# M2FS_FLS_Data_Formatter_8_14_2012.net
KiCad netlist of a schematic drawn in Altium Designer
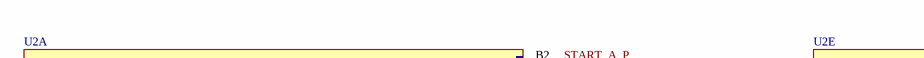
[diagram p0: M2FS FLS Data Formatter 8_14_2012.SchDoc, top right]
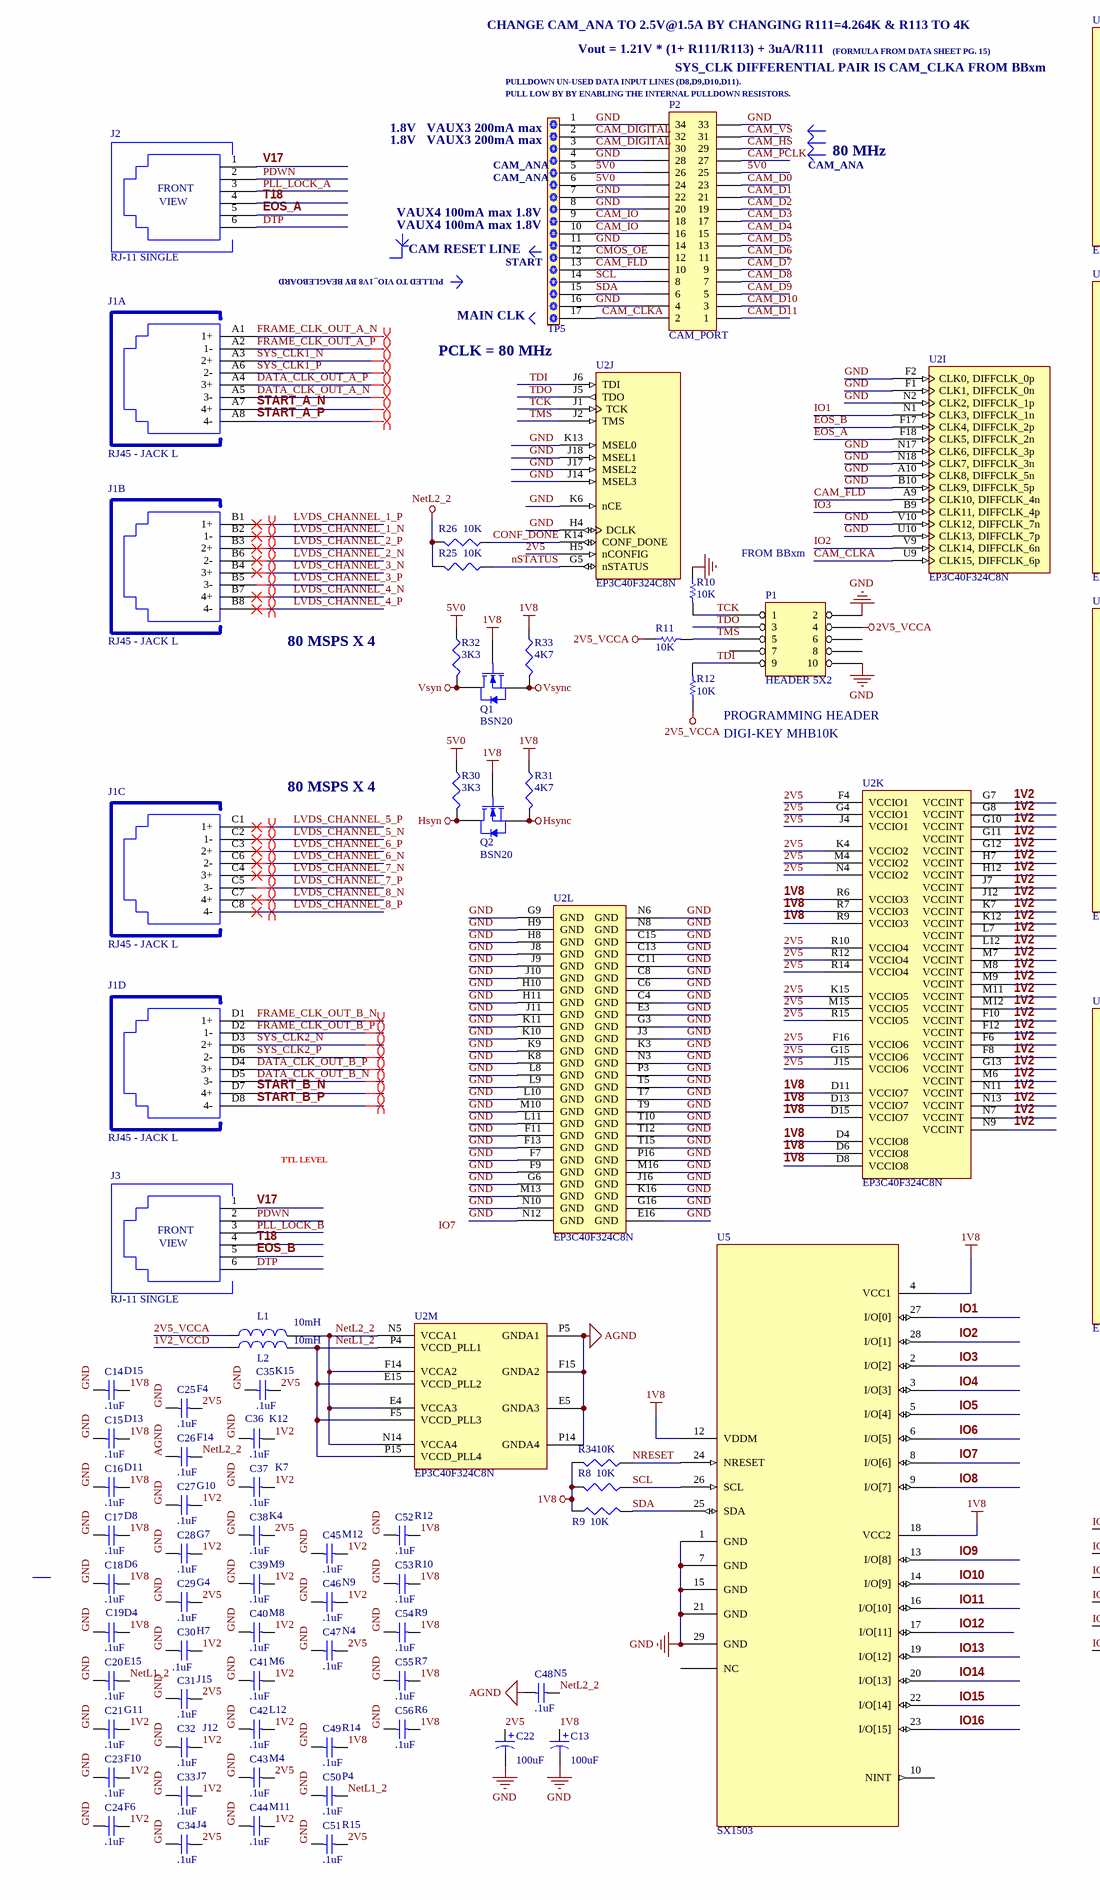
[diagram p1: M2FS FLS Data Formatter 8_14_2012.SchDoc, bottom left]
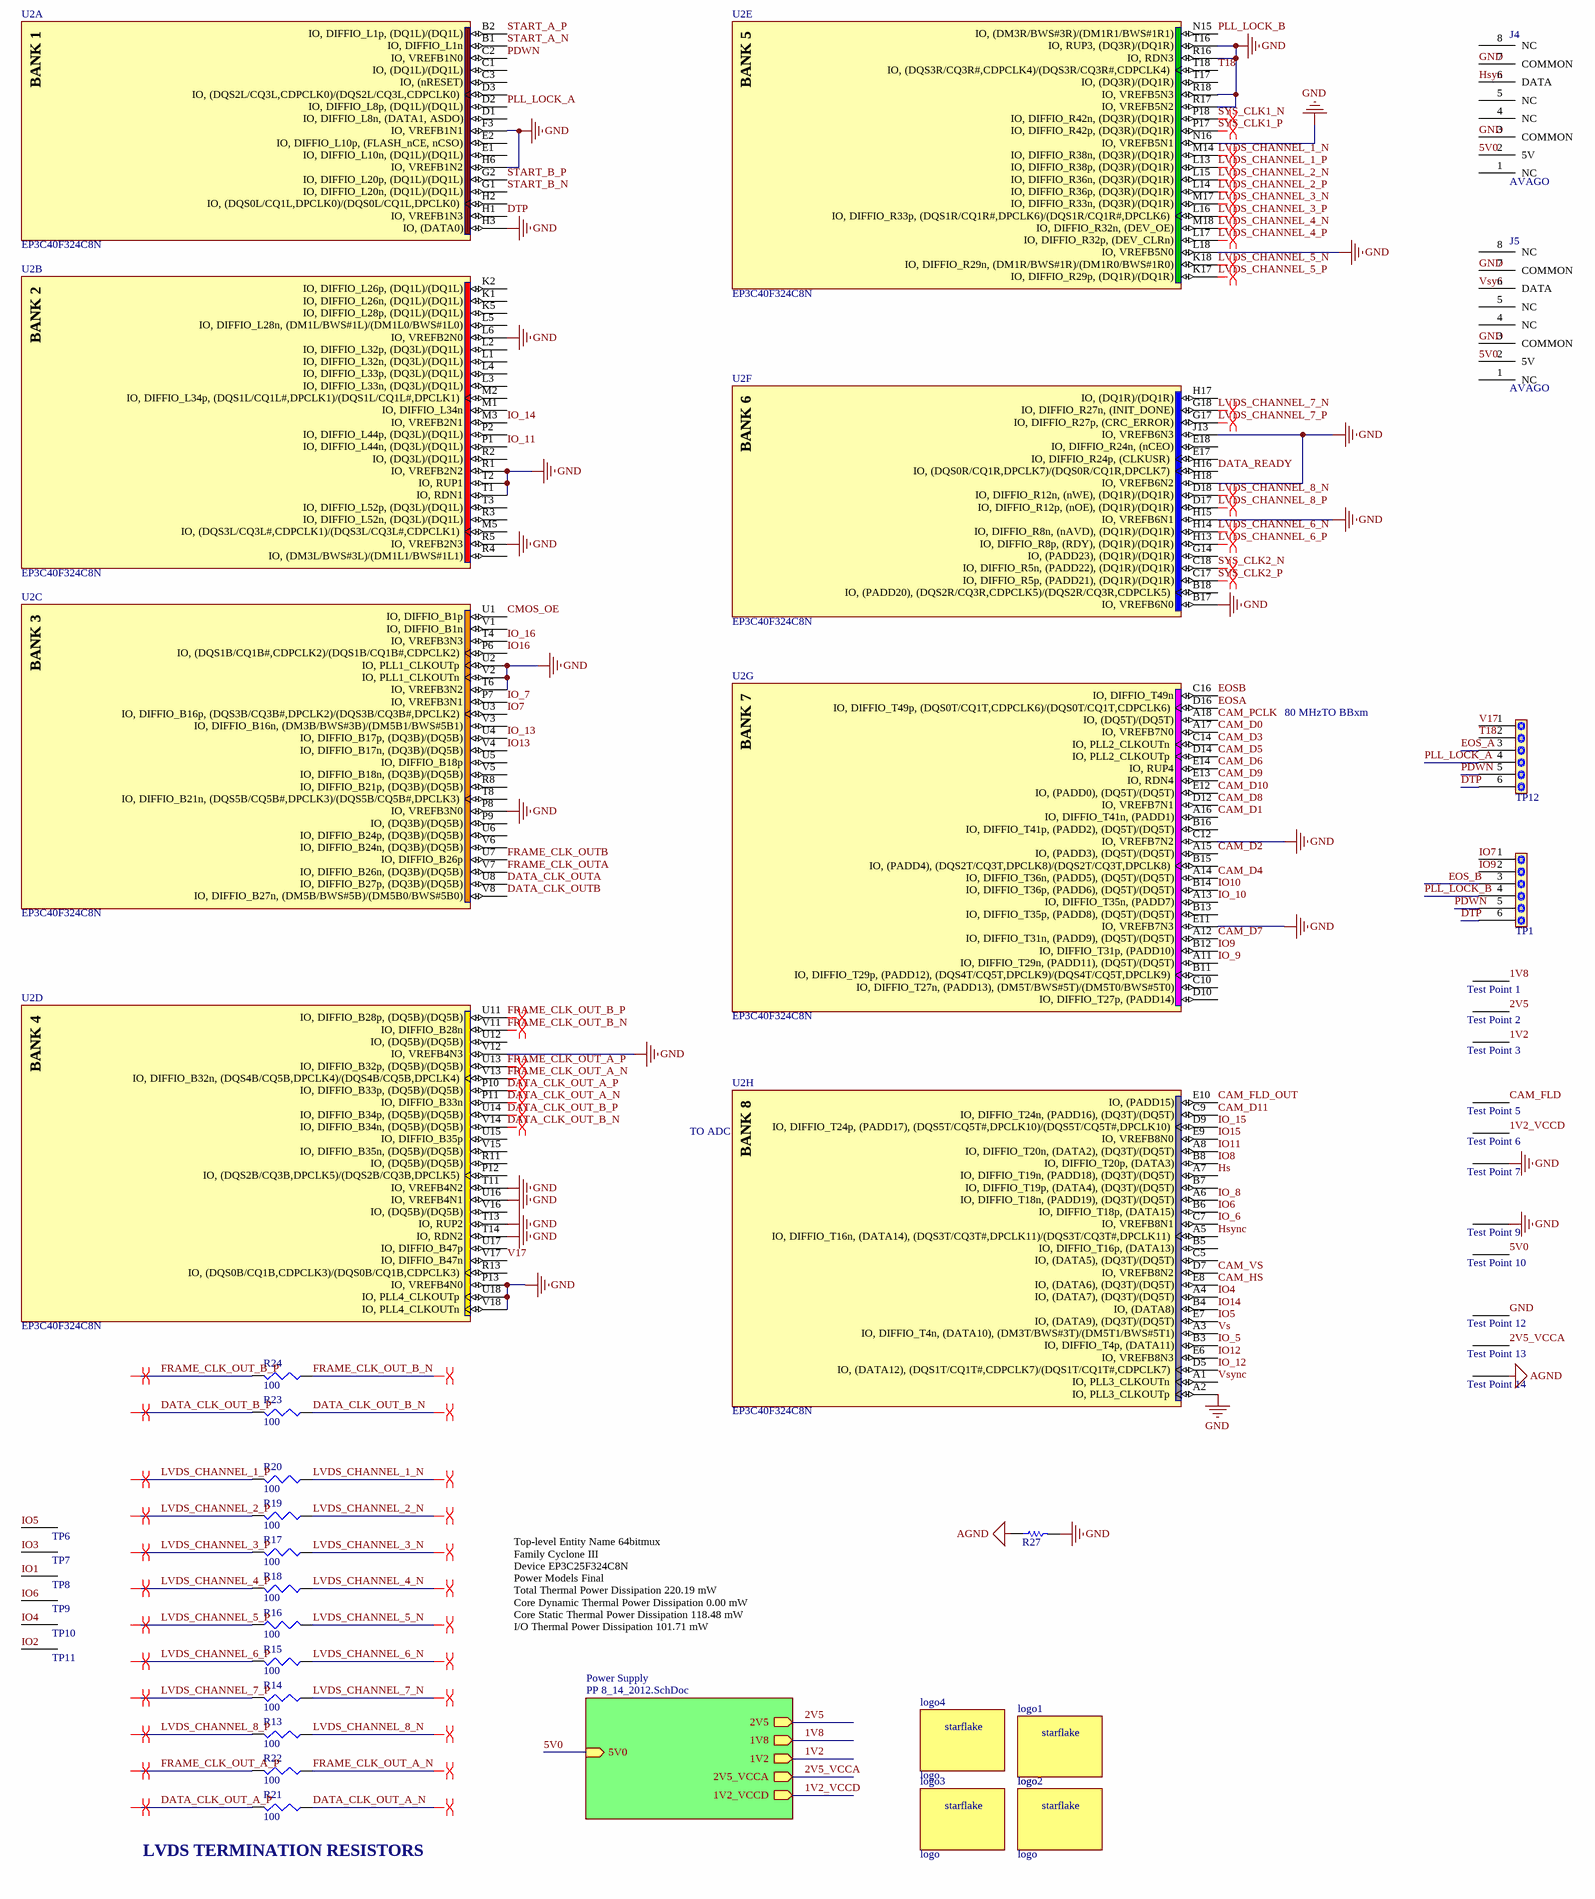
[diagram p2: M2FS FLS Data Formatter 8_14_2012.SchDoc, bottom right]

(export (version "E")
  (design (tool "Eeschema 10.0.6"))
  (components
    (comp (ref "C13")
      (value "100uF")
      (footprint "1206")
      (description "CAP TANT 100UF 10V 20% 1210")
      (fields (field (name "PUBLISHER") "Altium Limited"))
      (libsource (lib "Miscellaneous Devices") (part "Cap Pol3"))
    )
    (comp (ref "C14")
      (value ".1uF")
      (footprint "0402 slim")
      (description "CAP CER 0.1UF 25V Y5V 0805")
      (fields
        (field (name "BALL") "D15")
        (field (name "Comment") "0.1uF")
        (field (name "PUBLISHER") "Altium Limited")
      )
      (libsource (lib "Miscellaneous Devices") (part "Cap Semi"))
    )
    (comp (ref "C15")
      (value ".1uF")
      (footprint "0402 slim")
      (description "CAP CER 0.1UF 25V Y5V 0805")
      (fields
        (field (name "BALL") "D13")
        (field (name "Comment") "0.1uF")
        (field (name "PUBLISHER") "Altium Limited")
      )
      (libsource (lib "Miscellaneous Devices") (part "Cap Semi"))
    )
    (comp (ref "C16")
      (value ".1uF")
      (footprint "0402 slim-B")
      (description "CAP CER 0.1UF 25V Y5V 0805")
      (fields
        (field (name "BALL") "D11")
        (field (name "Comment") "0.1uF")
        (field (name "PUBLISHER") "Altium Limited")
      )
      (libsource (lib "Miscellaneous Devices") (part "Cap Semi"))
    )
    (comp (ref "C17")
      (value ".1uF")
      (footprint "0402 slim")
      (description "CAP CER 0.1UF 25V Y5V 0805")
      (fields
        (field (name "BALL") "D8")
        (field (name "Comment") "0.1uF")
        (field (name "PUBLISHER") "Altium Limited")
      )
      (libsource (lib "Miscellaneous Devices") (part "Cap Semi"))
    )
    (comp (ref "C18")
      (value ".1uF")
      (footprint "0402 slim-B")
      (description "CAP CER 0.1UF 25V Y5V 0805")
      (fields
        (field (name "BALL") "D6")
        (field (name "Comment") "0.1uF")
        (field (name "PUBLISHER") "Altium Limited")
      )
      (libsource (lib "Miscellaneous Devices") (part "Cap Semi"))
    )
    (comp (ref "C19")
      (value ".1uF")
      (footprint "0402 slim")
      (description "CAP CER 0.1UF 25V Y5V 0805")
      (fields
        (field (name "BALL") "D4")
        (field (name "Comment") "0.1uF")
        (field (name "PUBLISHER") "Altium Limited")
      )
      (libsource (lib "Miscellaneous Devices") (part "Cap Semi"))
    )
    (comp (ref "C20")
      (value ".1uF")
      (footprint "0402 slim-B")
      (description "CAP CER 0.1UF 25V Y5V 0805")
      (fields
        (field (name "BALL") "E15")
        (field (name "Comment") "0.1uF")
        (field (name "PUBLISHER") "Altium Limited")
      )
      (libsource (lib "Miscellaneous Devices") (part "Cap Semi"))
    )
    (comp (ref "C21")
      (value ".1uF")
      (footprint "0402 slim")
      (description "CAP CER 0.1UF 25V Y5V 0805")
      (fields
        (field (name "BALL") "G11")
        (field (name "Comment") "0.1uF")
        (field (name "PUBLISHER") "Altium Limited")
      )
      (libsource (lib "Miscellaneous Devices") (part "Cap Semi"))
    )
    (comp (ref "C22")
      (value "100uF")
      (footprint "1206")
      (description "CAP TANT 100UF 10V 20% 1210")
      (fields (field (name "PUBLISHER") "Altium Limited"))
      (libsource (lib "Miscellaneous Devices") (part "Cap Pol3"))
    )
    (comp (ref "C23")
      (value ".1uF")
      (footprint "0402 slim-B")
      (description "CAP CER 0.1UF 25V Y5V 0805")
      (fields
        (field (name "BALL") "F10")
        (field (name "Comment") "0.1uF")
        (field (name "PUBLISHER") "Altium Limited")
      )
      (libsource (lib "Miscellaneous Devices") (part "Cap Semi"))
    )
    (comp (ref "C24")
      (value ".1uF")
      (footprint "0402 slim")
      (description "CAP CER 0.1UF 25V Y5V 0805")
      (fields
        (field (name "BALL") "F6")
        (field (name "Comment") "0.1uF")
        (field (name "PUBLISHER") "Altium Limited")
      )
      (libsource (lib "Miscellaneous Devices") (part "Cap Semi"))
    )
    (comp (ref "C25")
      (value ".1uF")
      (footprint "0402 slim")
      (description "CAP CER 0.1UF 25V Y5V 0805")
      (fields
        (field (name "BALL") "F4")
        (field (name "Comment") "0.1uF")
        (field (name "PUBLISHER") "Altium Limited")
      )
      (libsource (lib "Miscellaneous Devices") (part "Cap Semi"))
    )
    (comp (ref "C26")
      (value ".1uF")
      (footprint "0402 slim")
      (description "CAP CER 0.1UF 25V Y5V 0805")
      (fields
        (field (name "BALL") "F14")
        (field (name "Comment") "0.1uF")
        (field (name "PUBLISHER") "Altium Limited")
      )
      (libsource (lib "Miscellaneous Devices") (part "Cap Semi"))
    )
    (comp (ref "C27")
      (value ".1uF")
      (footprint "0402 slim")
      (description "CAP CER 0.1UF 25V Y5V 0805")
      (fields
        (field (name "BALL") "G10")
        (field (name "Comment") "0.1uF")
        (field (name "PUBLISHER") "Altium Limited")
      )
      (libsource (lib "Miscellaneous Devices") (part "Cap Semi"))
    )
    (comp (ref "C28")
      (value ".1uF")
      (footprint "0402 slim-B")
      (description "CAP CER 0.1UF 25V Y5V 0805")
      (fields
        (field (name "BALL") "G7")
        (field (name "Comment") "0.1uF")
        (field (name "PUBLISHER") "Altium Limited")
      )
      (libsource (lib "Miscellaneous Devices") (part "Cap Semi"))
    )
    (comp (ref "C29")
      (value ".1uF")
      (footprint "0402 slim")
      (description "CAP CER 0.1UF 25V Y5V 0805")
      (fields
        (field (name "BALL") "G4")
        (field (name "Comment") "0.1uF")
        (field (name "PUBLISHER") "Altium Limited")
      )
      (libsource (lib "Miscellaneous Devices") (part "Cap Semi"))
    )
    (comp (ref "C30")
      (value ".1uF")
      (footprint "0402 slim-B")
      (description "CAP CER 0.1UF 25V Y5V 0805")
      (fields
        (field (name "BALL") "H7")
        (field (name "Comment") "0.1uF")
        (field (name "PUBLISHER") "Altium Limited")
      )
      (libsource (lib "Miscellaneous Devices") (part "Cap Semi"))
    )
    (comp (ref "C31")
      (value ".1uF")
      (footprint "0402 slim")
      (description "CAP CER 0.1UF 25V Y5V 0805")
      (fields
        (field (name "BALL") "J15")
        (field (name "Comment") "0.1uF")
        (field (name "PUBLISHER") "Altium Limited")
      )
      (libsource (lib "Miscellaneous Devices") (part "Cap Semi"))
    )
    (comp (ref "C32")
      (value ".1uF")
      (footprint "0402 slim-B")
      (description "CAP CER 0.1UF 25V Y5V 0805")
      (fields
        (field (name "BALL") "J12")
        (field (name "Comment") "0.1uF")
        (field (name "PUBLISHER") "Altium Limited")
      )
      (libsource (lib "Miscellaneous Devices") (part "Cap Semi"))
    )
    (comp (ref "C33")
      (value ".1uF")
      (footprint "0402 slim-B")
      (description "CAP CER 0.1UF 25V Y5V 0805")
      (fields
        (field (name "BALL") "J7")
        (field (name "Comment") "0.1uF")
        (field (name "PUBLISHER") "Altium Limited")
      )
      (libsource (lib "Miscellaneous Devices") (part "Cap Semi"))
    )
    (comp (ref "C34")
      (value ".1uF")
      (footprint "0402 slim")
      (description "CAP CER 0.1UF 25V Y5V 0805")
      (fields
        (field (name "C34") "J4")
        (field (name "Comment") "0.1uF")
        (field (name "PUBLISHER") "Altium Limited")
      )
      (libsource (lib "Miscellaneous Devices") (part "Cap Semi"))
    )
    (comp (ref "C35")
      (value ".1uF")
      (footprint "0402 slim")
      (description "CAP CER 0.1UF 25V Y5V 0805")
      (fields
        (field (name "BALL") "K15")
        (field (name "Comment") "0.1uF")
        (field (name "PUBLISHER") "Altium Limited")
      )
      (libsource (lib "Miscellaneous Devices") (part "Cap Semi"))
    )
    (comp (ref "C36")
      (value ".1uF")
      (footprint "0402 slim")
      (description "CAP CER 0.1UF 25V Y5V 0805")
      (fields
        (field (name "BALL") "K12")
        (field (name "Comment") "0.1uF")
        (field (name "PUBLISHER") "Altium Limited")
      )
      (libsource (lib "Miscellaneous Devices") (part "Cap Semi"))
    )
    (comp (ref "C37")
      (value ".1uF")
      (footprint "0402 slim-B")
      (description "CAP CER 0.1UF 25V Y5V 0805")
      (fields
        (field (name "BALL") "K7")
        (field (name "Comment") "0.1uF")
        (field (name "PUBLISHER") "Altium Limited")
      )
      (libsource (lib "Miscellaneous Devices") (part "Cap Semi"))
    )
    (comp (ref "C38")
      (value ".1uF")
      (footprint "0402 slim")
      (description "CAP CER 0.1UF 25V Y5V 0805")
      (fields
        (field (name "BALL") "K4")
        (field (name "Comment") "0.1uF")
        (field (name "PUBLISHER") "Altium Limited")
      )
      (libsource (lib "Miscellaneous Devices") (part "Cap Semi"))
    )
    (comp (ref "C39")
      (value ".1uF")
      (footprint "0402 slim")
      (description "CAP CER 0.1UF 25V Y5V 0805")
      (fields
        (field (name "BALL") "M9")
        (field (name "Comment") "0.1uF")
        (field (name "PUBLISHER") "Altium Limited")
      )
      (libsource (lib "Miscellaneous Devices") (part "Cap Semi"))
    )
    (comp (ref "C40")
      (value ".1uF")
      (footprint "0402 slim-B")
      (description "CAP CER 0.1UF 25V Y5V 0805")
      (fields
        (field (name "BALL") "M8")
        (field (name "Comment") "0.1uF")
        (field (name "PUBLISHER") "Altium Limited")
      )
      (libsource (lib "Miscellaneous Devices") (part "Cap Semi"))
    )
    (comp (ref "C41")
      (value ".1uF")
      (footprint "0402 slim")
      (description "CAP CER 0.1UF 25V Y5V 0805")
      (fields
        (field (name "BALL") "M6")
        (field (name "Comment") "0.1uF")
        (field (name "PUBLISHER") "Altium Limited")
      )
      (libsource (lib "Miscellaneous Devices") (part "Cap Semi"))
    )
    (comp (ref "C42")
      (value ".1uF")
      (footprint "0402 slim")
      (description "CAP CER 0.1UF 25V Y5V 0805")
      (fields
        (field (name "BALL") "L12")
        (field (name "Comment") "0.1uF")
        (field (name "PUBLISHER") "Altium Limited")
      )
      (libsource (lib "Miscellaneous Devices") (part "Cap Semi"))
    )
    (comp (ref "C43")
      (value ".1uF")
      (footprint "0402 slim")
      (description "CAP CER 0.1UF 25V Y5V 0805")
      (fields
        (field (name "BALL") "M4")
        (field (name "Comment") "0.1uF")
        (field (name "PUBLISHER") "Altium Limited")
      )
      (libsource (lib "Miscellaneous Devices") (part "Cap Semi"))
    )
    (comp (ref "C44")
      (value ".1uF")
      (footprint "0402 slim")
      (description "CAP CER 0.1UF 25V Y5V 0805")
      (fields
        (field (name "BALL") "M11")
        (field (name "Comment") "0.1uF")
        (field (name "PUBLISHER") "Altium Limited")
      )
      (libsource (lib "Miscellaneous Devices") (part "Cap Semi"))
    )
    (comp (ref "C45")
      (value ".1uF")
      (footprint "0402 slim-B")
      (description "CAP CER 0.1UF 25V Y5V 0805")
      (fields
        (field (name "BALL") "M12")
        (field (name "Comment") "0.1uF")
        (field (name "PUBLISHER") "Altium Limited")
      )
      (libsource (lib "Miscellaneous Devices") (part "Cap Semi"))
    )
    (comp (ref "C46")
      (value ".1uF")
      (footprint "0402 slim")
      (description "CAP CER 0.1UF 25V Y5V 0805")
      (fields
        (field (name "BALL") "N9")
        (field (name "Comment") "0.1uF")
        (field (name "PUBLISHER") "Altium Limited")
      )
      (libsource (lib "Miscellaneous Devices") (part "Cap Semi"))
    )
    (comp (ref "C47")
      (value ".1uF")
      (footprint "0402 slim")
      (description "CAP CER 0.1UF 25V Y5V 0805")
      (fields
        (field (name "BAL") "N4")
        (field (name "Comment") "0.1uF")
        (field (name "PUBLISHER") "Altium Limited")
      )
      (libsource (lib "Miscellaneous Devices") (part "Cap Semi"))
    )
    (comp (ref "C48")
      (value ".1uF")
      (footprint "0402 slim")
      (description "CAP CER 0.1UF 25V Y5V 0805")
      (fields
        (field (name "BALL") "N5")
        (field (name "Comment") "0.1uF")
        (field (name "PUBLISHER") "Altium Limited")
      )
      (libsource (lib "Miscellaneous Devices") (part "Cap Semi"))
    )
    (comp (ref "C49")
      (value ".1uF")
      (footprint "0402 slim")
      (description "CAP CER 0.1UF 25V Y5V 0805")
      (fields
        (field (name "BALL") "R14")
        (field (name "Comment") "0.1uF")
        (field (name "PUBLISHER") "Altium Limited")
      )
      (libsource (lib "Miscellaneous Devices") (part "Cap Semi"))
    )
    (comp (ref "C50")
      (value ".1uF")
      (footprint "0402 slim")
      (description "CAP CER 0.1UF 25V Y5V 0805")
      (fields
        (field (name "BALL") "P4")
        (field (name "Comment") "0.1uF")
        (field (name "PUBLISHER") "Altium Limited")
      )
      (libsource (lib "Miscellaneous Devices") (part "Cap Semi"))
    )
    (comp (ref "C51")
      (value ".1uF")
      (footprint "0402 slim")
      (description "CAP CER 0.1UF 25V Y5V 0805")
      (fields
        (field (name "BALL") "R15")
        (field (name "Comment") "0.1uF")
        (field (name "PUBLISHER") "Altium Limited")
      )
      (libsource (lib "Miscellaneous Devices") (part "Cap Semi"))
    )
    (comp (ref "C52")
      (value ".1uF")
      (footprint "0402 slim")
      (description "CAP CER 0.1UF 25V Y5V 0805")
      (fields
        (field (name "BALL") "R12")
        (field (name "Comment") "0.1uF")
        (field (name "PUBLISHER") "Altium Limited")
      )
      (libsource (lib "Miscellaneous Devices") (part "Cap Semi"))
    )
    (comp (ref "C53")
      (value ".1uF")
      (footprint "0402 slim")
      (description "CAP CER 0.1UF 25V Y5V 0805")
      (fields
        (field (name "BALL") "R10")
        (field (name "Comment") "0.1uF")
        (field (name "PUBLISHER") "Altium Limited")
      )
      (libsource (lib "Miscellaneous Devices") (part "Cap Semi"))
    )
    (comp (ref "C54")
      (value ".1uF")
      (footprint "0402 slim")
      (description "CAP CER 0.1UF 25V Y5V 0805")
      (fields
        (field (name "BALL") "R9")
        (field (name "Comment") "0.1uF")
        (field (name "PUBLISHER") "Altium Limited")
      )
      (libsource (lib "Miscellaneous Devices") (part "Cap Semi"))
    )
    (comp (ref "C55")
      (value ".1uF")
      (footprint "0402 slim")
      (description "CAP CER 0.1UF 25V Y5V 0805")
      (fields
        (field (name "BALL") "R7")
        (field (name "Comment") "0.1uF")
        (field (name "PUBLISHER") "Altium Limited")
      )
      (libsource (lib "Miscellaneous Devices") (part "Cap Semi"))
    )
    (comp (ref "C56")
      (value ".1uF")
      (footprint "0402 slim")
      (description "CAP CER 0.1UF 25V Y5V 0805")
      (fields
        (field (name "BALL") "R6")
        (field (name "Comment") "0.1uF")
        (field (name "PUBLISHER") "Altium Limited")
      )
      (libsource (lib "Miscellaneous Devices") (part "Cap Semi"))
    )
    (comp (ref "J1")
      (value "RJ45 - JACK L")
      (footprint "5558503-1 Quad RJ45 Jack")
      (description "CONN MOD JACK 4PORT5 8-8 SHLD PCB")
      (fields
        (field (name "DIGI-KEY PART NUMBER") "A31470-ND")
        (field (name "MANUFACTURER") "TE Connectivity")
      )
      (libsource (lib "FLS Data Formatter 8_14_2012") (part "RJ45 - JACK L"))
    )
    (comp (ref "J2")
      (value "RJ-11 SINGLE")
      (footprint "RJ11 - 5555140-1")
      (description "RJ-11 JACK")
      (libsource (lib "FLS Data Formatter 8_14_2012") (part "RJ-11 SINGLE"))
    )
    (comp (ref "J3")
      (value "RJ-11 SINGLE")
      (footprint "RJ11 - 5555140-1")
      (description "RJ-11 JACK")
      (libsource (lib "FLS Data Formatter 8_14_2012") (part "RJ-11 SINGLE"))
    )
    (comp (ref "J4")
      (value "AVAGO")
      (footprint "HFBR-2412Z")
      (libsource (lib "FLS Data Formatter 8_14_2012") (part "HFBR-2412"))
    )
    (comp (ref "J5")
      (value "AVAGO")
      (footprint "HFBR-2412Z")
      (libsource (lib "FLS Data Formatter 8_14_2012") (part "HFBR-2412"))
    )
    (comp (ref "L1")
      (value "10mH")
      (footprint "0805")
      (description "Inductor")
      (fields (field (name "PUBLISHER") "Altium Limited"))
      (libsource (lib "Miscellaneous Devices") (part "Inductor"))
    )
    (comp (ref "L2")
      (value "10mH")
      (footprint "0805")
      (description "Inductor")
      (fields (field (name "PUBLISHER") "Altium Limited"))
      (libsource (lib "Miscellaneous Devices") (part "Inductor"))
    )
    (comp (ref "logo1")
      (value "logo")
      (footprint "STARFLAKE")
      (libsource (lib "FLS Data Formatter 8_14_2012") (part "starflake"))
    )
    (comp (ref "logo2")
      (value "logo")
      (footprint "STARFLAKE")
      (libsource (lib "FLS Data Formatter 8_14_2012") (part "starflake"))
    )
    (comp (ref "logo3")
      (value "logo")
      (footprint "STARFLAKE")
      (libsource (lib "FLS Data Formatter 8_14_2012") (part "starflake"))
    )
    (comp (ref "logo4")
      (value "logo")
      (footprint "STARFLAKE")
      (libsource (lib "FLS Data Formatter 8_14_2012") (part "starflake"))
    )
    (comp (ref "P1")
      (value "HEADER 5X2")
      (footprint "HDR2X5")
      (libsource (lib "FLS Data Formatter 8_14_2012") (part "HEADER 5X2"))
    )
    (comp (ref "P2")
      (value "CAM_PORT")
      (footprint "CON34_.05X.05")
      (description "Header, 17-Pin, Dual row")
      (fields (field (name "PUBLISHER") "Altium Limited"))
      (libsource (lib "Miscellaneous Connectors") (part "Header 17X2"))
    )
    (comp (ref "Q1")
      (value "BSN20")
      (footprint "SOT23")
      (description "N-channel Enhancement Mode FET")
      (fields (field (name "PUBLISHER") "Altium Limited"))
      (libsource (lib "Philips Discrete MOSFET - Low Power") (part "BSN20"))
    )
    (comp (ref "Q2")
      (value "BSN20")
      (footprint "SOT23")
      (description "N-channel Enhancement Mode FET")
      (fields (field (name "PUBLISHER") "Altium Limited"))
      (libsource (lib "Philips Discrete MOSFET - Low Power") (part "BSN20"))
    )
    (comp (ref "R8")
      (value "10K")
      (footprint "0402 slim")
      (libsource (lib "FLS Data Formatter 8_14_2012") (part "RES1"))
    )
    (comp (ref "R9")
      (value "10K")
      (footprint "0402 slim")
      (libsource (lib "FLS Data Formatter 8_14_2012") (part "RES1"))
    )
    (comp (ref "R10")
      (value "10K")
      (footprint "6-0805")
      (fields
        (field (name "MANUFACTURER") "Panasonic")
        (field (name "DIGIKEY PART #") "P10KATR-ND")
        (field (name "PUBLISHER") "Altium Limited")
      )
      (libsource (lib "Panasonic Resistor") (part "ERJ6RK"))
    )
    (comp (ref "R11")
      (value "10K")
      (footprint "6-0805")
      (fields
        (field (name "MANUFACTURER") "Panasonic")
        (field (name "DIGIKEY PART #") "P10KATR-ND")
        (field (name "PUBLISHER") "Altium Limited")
      )
      (libsource (lib "Panasonic Resistor") (part "ERJ6RK"))
    )
    (comp (ref "R12")
      (value "10K")
      (footprint "6-0805")
      (fields
        (field (name "MANUFACTURER") "Panasonic")
        (field (name "DIGIKEY PART #") "P10KATR-ND")
        (field (name "PUBLISHER") "Altium Limited")
      )
      (libsource (lib "Panasonic Resistor") (part "ERJ6RK"))
    )
    (comp (ref "R13")
      (value "100")
      (footprint "0402 slim")
      (libsource (lib "FLS Data Formatter 8_14_2012") (part "RES1"))
    )
    (comp (ref "R14")
      (value "100")
      (footprint "0402 slim")
      (libsource (lib "FLS Data Formatter 8_14_2012") (part "RES1"))
    )
    (comp (ref "R15")
      (value "100")
      (footprint "0402 slim")
      (libsource (lib "FLS Data Formatter 8_14_2012") (part "RES1"))
    )
    (comp (ref "R16")
      (value "100")
      (footprint "0402 slim")
      (libsource (lib "FLS Data Formatter 8_14_2012") (part "RES1"))
    )
    (comp (ref "R17")
      (value "100")
      (footprint "0402 one-of")
      (libsource (lib "FLS Data Formatter 8_14_2012") (part "RES1"))
    )
    (comp (ref "R18")
      (value "100")
      (footprint "0402 slim")
      (libsource (lib "FLS Data Formatter 8_14_2012") (part "RES1"))
    )
    (comp (ref "R19")
      (value "100")
      (footprint "0402 slim")
      (libsource (lib "FLS Data Formatter 8_14_2012") (part "RES1"))
    )
    (comp (ref "R20")
      (value "100")
      (footprint "0402 slim")
      (libsource (lib "FLS Data Formatter 8_14_2012") (part "RES1"))
    )
    (comp (ref "R21")
      (value "100")
      (footprint "0402 slim")
      (libsource (lib "FLS Data Formatter 8_14_2012") (part "RES1"))
    )
    (comp (ref "R22")
      (value "100")
      (footprint "0402 slim")
      (libsource (lib "FLS Data Formatter 8_14_2012") (part "RES1"))
    )
    (comp (ref "R23")
      (value "100")
      (footprint "0402 slim")
      (libsource (lib "FLS Data Formatter 8_14_2012") (part "RES1"))
    )
    (comp (ref "R24")
      (value "100")
      (footprint "0402 slim")
      (libsource (lib "FLS Data Formatter 8_14_2012") (part "RES1"))
    )
    (comp (ref "R25")
      (value "10K")
      (footprint "0805")
      (libsource (lib "FLS Data Formatter 8_14_2012") (part "RES1"))
    )
    (comp (ref "R26")
      (value "10K")
      (footprint "0805")
      (libsource (lib "FLS Data Formatter 8_14_2012") (part "RES1"))
    )
    (comp (ref "R27")
      (value "0R5 0805(2012)")
      (footprint "RESC0805(2012)_N")
      (description "0R5 0805 (2012 Metric)")
      (fields (field (name "TOLERANCE") "1%") (field (name "POWER") "None"))
      (libsource (lib "Altium Vault") (part "CMP-1013-00001-1"))
    )
    (comp (ref "R30")
      (value "3K3")
      (footprint "0805")
      (libsource (lib "FLS Data Formatter 8_14_2012") (part "RES1"))
    )
    (comp (ref "R31")
      (value "4K7")
      (footprint "0805")
      (libsource (lib "FLS Data Formatter 8_14_2012") (part "RES1"))
    )
    (comp (ref "R32")
      (value "3K3")
      (footprint "0805")
      (libsource (lib "FLS Data Formatter 8_14_2012") (part "RES1"))
    )
    (comp (ref "R33")
      (value "4K7")
      (footprint "0805")
      (libsource (lib "FLS Data Formatter 8_14_2012") (part "RES1"))
    )
    (comp (ref "R34")
      (value "10K")
      (footprint "0402 slim")
      (libsource (lib "FLS Data Formatter 8_14_2012") (part "RES1"))
    )
    (comp (ref "Test Point 1") (value "TP-107") (libsource (lib "FLS ADC_A") (part "TP-107")))
    (comp (ref "Test Point 2") (value "TP-107") (libsource (lib "FLS ADC_A") (part "TP-107")))
    (comp (ref "Test Point 3") (value "TP-107") (libsource (lib "FLS ADC_A") (part "TP-107")))
    (comp (ref "Test Point 5") (value "TP-107") (libsource (lib "FLS ADC_A") (part "TP-107")))
    (comp (ref "Test Point 6")
      (value "TP-107")
      (footprint "TP-107")
      (libsource (lib "FLS ADC_A") (part "TP-107"))
    )
    (comp (ref "Test Point 7") (value "TP-107") (libsource (lib "FLS ADC_A") (part "TP-107")))
    (comp (ref "Test Point 9") (value "TP-107") (libsource (lib "FLS ADC_A") (part "TP-107")))
    (comp (ref "Test Point 10") (value "TP-107") (libsource (lib "FLS ADC_A") (part "TP-107")))
    (comp (ref "Test Point 12")
      (value "TP-107")
      (footprint "TP-107")
      (libsource (lib "FLS ADC_A") (part "TP-107"))
    )
    (comp (ref "Test Point 13")
      (value "TP-107")
      (footprint "TP-107")
      (libsource (lib "FLS ADC_A") (part "TP-107"))
    )
    (comp (ref "Test Point 14")
      (value "TP-107")
      (footprint "TP-107")
      (libsource (lib "FLS ADC_A") (part "TP-107"))
    )
    (comp (ref "TP1")
      (value "TP6")
      (footprint "TP6")
      (libsource (lib "FLS Data Formatter 8_14_2012") (part "TP6"))
    )
    (comp (ref "TP5")
      (value "TP17")
      (footprint "TP17")
      (description "Test Point")
      (libsource (lib "FLS Data Formatter 8_14_2012") (part "TP17"))
    )
    (comp (ref "TP6")
      (value "IO5")
      (footprint "TP1")
      (libsource (lib "FLS Data Formatter 8_14_2012") (part "TP1"))
    )
    (comp (ref "TP7")
      (value "IO3")
      (footprint "TP1")
      (libsource (lib "FLS Data Formatter 8_14_2012") (part "TP1"))
    )
    (comp (ref "TP8")
      (value "IO1")
      (footprint "TP1")
      (libsource (lib "FLS Data Formatter 8_14_2012") (part "TP1"))
    )
    (comp (ref "TP9")
      (value "IO6")
      (footprint "TP1")
      (libsource (lib "FLS Data Formatter 8_14_2012") (part "TP1"))
    )
    (comp (ref "TP10")
      (value "IO4")
      (footprint "TP1")
      (libsource (lib "FLS Data Formatter 8_14_2012") (part "TP1"))
    )
    (comp (ref "TP11")
      (value "IO2")
      (footprint "TP1")
      (libsource (lib "FLS Data Formatter 8_14_2012") (part "TP1"))
    )
    (comp (ref "TP12")
      (value "TP6")
      (footprint "TP6")
      (libsource (lib "FLS Data Formatter 8_14_2012") (part "TP6"))
    )
    (comp (ref "U2")
      (value "EP3C40F324C8N")
      (footprint "FBGA324")
      (fields (field (name "PUBLISHER") "Altium Limited"))
      (libsource (lib "Altera Cyclone III") (part "EP3C40F324C8N"))
    )
    (comp (ref "U5")
      (value "SX1503")
      (footprint "QFN-UT28")
      (description "i2C LV GPIO")
      (libsource (lib "FLS Data Formatter 8_14_2012") (part "SX1503"))
    )
  )
  (nets
    (net (code "1") (name "/1V2") (class "Default")
      (node (ref "C21") (pin "1") (pinfunction "1_1") (pintype "passive"))
      (node (ref "C23") (pin "2") (pinfunction "2_2") (pintype "passive"))
      (node (ref "C24") (pin "1") (pinfunction "1_1") (pintype "passive"))
      (node (ref "C27") (pin "1") (pinfunction "1_1") (pintype "passive"))
      (node (ref "C28") (pin "2") (pinfunction "2_2") (pintype "passive"))
      (node (ref "C30") (pin "2") (pinfunction "2_2") (pintype "passive"))
      (node (ref "C32") (pin "2") (pinfunction "2_2") (pintype "passive"))
      (node (ref "C33") (pin "2") (pinfunction "2_2") (pintype "passive"))
      (node (ref "C36") (pin "1") (pinfunction "1_1") (pintype "passive"))
      (node (ref "C37") (pin "2") (pinfunction "2_2") (pintype "passive"))
      (node (ref "C39") (pin "1") (pinfunction "1_1") (pintype "passive"))
      (node (ref "C40") (pin "2") (pinfunction "2_2") (pintype "passive"))
      (node (ref "C41") (pin "1") (pinfunction "1_1") (pintype "passive"))
      (node (ref "C42") (pin "1") (pinfunction "1_1") (pintype "passive"))
      (node (ref "C44") (pin "1") (pinfunction "1_1") (pintype "passive"))
      (node (ref "C45") (pin "2") (pinfunction "2_2") (pintype "passive"))
      (node (ref "C46") (pin "1") (pinfunction "1_1") (pintype "passive"))
      (node (ref "Test Point 3") (pin "1") (pinfunction "1_1") (pintype "passive"))
      (node (ref "U2") (pin "F10") (pinfunction "VCCINT_F10") (pintype "power_in"))
      (node (ref "U2") (pin "F12") (pinfunction "VCCINT_F12") (pintype "power_in"))
      (node (ref "U2") (pin "F6") (pinfunction "VCCINT_F6") (pintype "power_in"))
      (node (ref "U2") (pin "F8") (pinfunction "VCCINT_F8") (pintype "power_in"))
      (node (ref "U2") (pin "G10") (pinfunction "VCCINT_G10") (pintype "power_in"))
      (node (ref "U2") (pin "G11") (pinfunction "VCCINT_G11") (pintype "power_in"))
      (node (ref "U2") (pin "G12") (pinfunction "VCCINT_G12") (pintype "power_in"))
      (node (ref "U2") (pin "G13") (pinfunction "VCCINT_G13") (pintype "power_in"))
      (node (ref "U2") (pin "G7") (pinfunction "VCCINT_G7") (pintype "power_in"))
      (node (ref "U2") (pin "G8") (pinfunction "VCCINT_G8") (pintype "power_in"))
      (node (ref "U2") (pin "H12") (pinfunction "VCCINT_H12") (pintype "power_in"))
      (node (ref "U2") (pin "H7") (pinfunction "VCCINT_H7") (pintype "power_in"))
      (node (ref "U2") (pin "J12") (pinfunction "VCCINT_J12") (pintype "power_in"))
      (node (ref "U2") (pin "J7") (pinfunction "VCCINT_J7") (pintype "power_in"))
      (node (ref "U2") (pin "K12") (pinfunction "VCCINT_K12") (pintype "power_in"))
      (node (ref "U2") (pin "K7") (pinfunction "VCCINT_K7") (pintype "power_in"))
      (node (ref "U2") (pin "L12") (pinfunction "VCCINT_L12") (pintype "power_in"))
      (node (ref "U2") (pin "L7") (pinfunction "VCCINT_L7") (pintype "power_in"))
      (node (ref "U2") (pin "M11") (pinfunction "VCCINT_M11") (pintype "power_in"))
      (node (ref "U2") (pin "M12") (pinfunction "VCCINT_M12") (pintype "power_in"))
      (node (ref "U2") (pin "M6") (pinfunction "VCCINT_M6") (pintype "power_in"))
      (node (ref "U2") (pin "M7") (pinfunction "VCCINT_M7") (pintype "power_in"))
      (node (ref "U2") (pin "M8") (pinfunction "VCCINT_M8") (pintype "power_in"))
      (node (ref "U2") (pin "M9") (pinfunction "VCCINT_M9") (pintype "power_in"))
      (node (ref "U2") (pin "N11") (pinfunction "VCCINT_N11") (pintype "power_in"))
      (node (ref "U2") (pin "N13") (pinfunction "VCCINT_N13") (pintype "power_in"))
      (node (ref "U2") (pin "N7") (pinfunction "VCCINT_N7") (pintype "power_in"))
      (node (ref "U2") (pin "N9") (pinfunction "VCCINT_N9") (pintype "power_in"))
    )
    (net (code "2") (name "/1V2_VCCD") (class "Default")
      (node (ref "L2") (pin "1") (pinfunction "1_1") (pintype "passive"))
      (node (ref "Test Point 6") (pin "1") (pinfunction "1_1") (pintype "passive"))
    )
    (net (code "3") (name "/2V5") (class "Default")
      (node (ref "C22") (pin "1") (pinfunction "1_1") (pintype "passive"))
      (node (ref "C25") (pin "1") (pinfunction "1_1") (pintype "passive"))
      (node (ref "C29") (pin "1") (pinfunction "1_1") (pintype "passive"))
      (node (ref "C31") (pin "2") (pinfunction "2_2") (pintype "passive"))
      (node (ref "C34") (pin "1") (pinfunction "1_1") (pintype "passive"))
      (node (ref "C35") (pin "1") (pinfunction "1_1") (pintype "passive"))
      (node (ref "C38") (pin "1") (pinfunction "1_1") (pintype "passive"))
      (node (ref "C43") (pin "1") (pinfunction "1_1") (pintype "passive"))
      (node (ref "C47") (pin "1") (pinfunction "1_1") (pintype "passive"))
      (node (ref "C51") (pin "2") (pinfunction "2_2") (pintype "passive"))
      (node (ref "Test Point 2") (pin "1") (pinfunction "1_1") (pintype "passive"))
      (node (ref "U2") (pin "F16") (pinfunction "VCCIO6_F16") (pintype "power_in"))
      (node (ref "U2") (pin "F4") (pinfunction "VCCIO1_F4") (pintype "power_in"))
      (node (ref "U2") (pin "G15") (pinfunction "VCCIO6_G15") (pintype "power_in"))
      (node (ref "U2") (pin "G4") (pinfunction "VCCIO1_G4") (pintype "power_in"))
      (node (ref "U2") (pin "H5") (pinfunction "nCONFIG_H5") (pintype "input"))
      (node (ref "U2") (pin "J15") (pinfunction "VCCIO6_J15") (pintype "power_in"))
      (node (ref "U2") (pin "J4") (pinfunction "VCCIO1_J4") (pintype "power_in"))
      (node (ref "U2") (pin "K15") (pinfunction "VCCIO5_K15") (pintype "power_in"))
      (node (ref "U2") (pin "K4") (pinfunction "VCCIO2_K4") (pintype "power_in"))
      (node (ref "U2") (pin "M15") (pinfunction "VCCIO5_M15") (pintype "power_in"))
      (node (ref "U2") (pin "M4") (pinfunction "VCCIO2_M4") (pintype "power_in"))
      (node (ref "U2") (pin "N4") (pinfunction "VCCIO2_N4") (pintype "power_in"))
      (node (ref "U2") (pin "R10") (pinfunction "VCCIO4_R10") (pintype "power_in"))
      (node (ref "U2") (pin "R12") (pinfunction "VCCIO4_R12") (pintype "power_in"))
      (node (ref "U2") (pin "R14") (pinfunction "VCCIO4_R14") (pintype "power_in"))
      (node (ref "U2") (pin "R15") (pinfunction "VCCIO5_R15") (pintype "power_in"))
    )
    (net (code "4") (name "/CAM_CLKA") (class "Default")
      (node (ref "P2") (pin "2") (pinfunction "2_2") (pintype "passive"))
      (node (ref "TP5") (pin "17") (pinfunction "17_17") (pintype "power_in"))
      (node (ref "U2") (pin "U9") (pinfunction "CLK15,_DIFFCLK_6p_U9") (pintype "input"))
    )
    (net (code "5") (name "/CAM_D0") (class "Default")
      (node (ref "P2") (pin "23") (pinfunction "23_23") (pintype "passive"))
      (node (ref "U2") (pin "A17") (pinfunction "IO,_VREFB7N0_A17") (pintype "bidirectional"))
    )
    (net (code "6") (name "/CAM_D1") (class "Default")
      (node (ref "P2") (pin "21") (pinfunction "21_21") (pintype "passive"))
      (node (ref "U2") (pin "A16") (pinfunction "IO,_DIFFIO_T41n,_(PADD1)_A16") (pintype "bidirectional"))
    )
    (net (code "7") (name "/CAM_D2") (class "Default")
      (node (ref "P2") (pin "19") (pinfunction "19_19") (pintype "passive"))
      (node (ref "U2") (pin "A15") (pinfunction "IO,_(PADD3),_(DQ5T)/(DQ5T)_A15") (pintype "bidirectional"))
    )
    (net (code "8") (name "/CAM_D3") (class "Default")
      (node (ref "P2") (pin "17") (pinfunction "17_17") (pintype "passive"))
      (node (ref "U2") (pin "C14") (pinfunction "IO,_PLL2_CLKOUTn_C14") (pintype "bidirectional"))
    )
    (net (code "9") (name "/CAM_D4") (class "Default")
      (node (ref "P2") (pin "15") (pinfunction "15_15") (pintype "passive"))
      (node (ref "U2") (pin "A14") (pinfunction "IO,_DIFFIO_T36n,_(PADD5),_(DQ5T)/(DQ5T)_A14") (pintype "bidirectional"))
    )
    (net (code "10") (name "/CAM_D5") (class "Default")
      (node (ref "P2") (pin "13") (pinfunction "13_13") (pintype "passive"))
      (node (ref "U2") (pin "D14") (pinfunction "IO,_PLL2_CLKOUTp_D14") (pintype "bidirectional"))
    )
    (net (code "11") (name "/CAM_D6") (class "Default")
      (node (ref "P2") (pin "11") (pinfunction "11_11") (pintype "passive"))
      (node (ref "U2") (pin "E14") (pinfunction "IO,_RUP4_E14") (pintype "bidirectional"))
    )
    (net (code "12") (name "/CAM_D7") (class "Default")
      (node (ref "P2") (pin "9") (pinfunction "9_9") (pintype "passive"))
      (node (ref "U2") (pin "A12") (pinfunction "IO,_DIFFIO_T31n,_(PADD9),_(DQ5T)/(DQ5T)_A12") (pintype "bidirectional"))
    )
    (net (code "13") (name "/CAM_D8") (class "Default")
      (node (ref "P2") (pin "7") (pinfunction "7_7") (pintype "passive"))
      (node (ref "U2") (pin "D12") (pinfunction "IO,_VREFB7N1_D12") (pintype "bidirectional"))
    )
    (net (code "14") (name "/CAM_D9") (class "Default")
      (node (ref "P2") (pin "5") (pinfunction "5_5") (pintype "passive"))
      (node (ref "U2") (pin "E13") (pinfunction "IO,_RDN4_E13") (pintype "bidirectional"))
    )
    (net (code "15") (name "/CAM_D10") (class "Default")
      (node (ref "P2") (pin "3") (pinfunction "3_3") (pintype "passive"))
      (node (ref "U2") (pin "E12") (pinfunction "IO,_(PADD0),_(DQ5T)/(DQ5T)_E12") (pintype "bidirectional"))
    )
    (net (code "16") (name "/CAM_D11") (class "Default")
      (node (ref "P2") (pin "1") (pinfunction "1_1") (pintype "passive"))
      (node (ref "U2") (pin "C9") (pinfunction "IO,_DIFFIO_T24n,_(PADD16),_(DQ3T)/(DQ5T)_C9") (pintype "bidirectional"))
    )
    (net (code "17") (name "/CAM_DIGITAL") (class "Default")
      (node (ref "P2") (pin "30") (pinfunction "30_30") (pintype "passive"))
      (node (ref "P2") (pin "32") (pinfunction "32_32") (pintype "passive"))
      (node (ref "TP5") (pin "2") (pinfunction "2_2") (pintype "power_in"))
      (node (ref "TP5") (pin "3") (pinfunction "3_3") (pintype "power_in"))
    )
    (net (code "18") (name "/CAM_FLD") (class "Default")
      (node (ref "P2") (pin "10") (pinfunction "10_10") (pintype "passive"))
      (node (ref "TP5") (pin "13") (pinfunction "13_13") (pintype "power_in"))
      (node (ref "Test Point 5") (pin "1") (pinfunction "1_1") (pintype "passive"))
      (node (ref "U2") (pin "A9") (pinfunction "CLK10,_DIFFCLK_4n_A9") (pintype "input"))
    )
    (net (code "19") (name "/CAM_FLD_OUT") (class "Default")
      (node (ref "U2") (pin "E10") (pinfunction "IO,_(PADD15)_E10") (pintype "bidirectional"))
    )
    (net (code "20") (name "/CAM_HS") (class "Default")
      (node (ref "P2") (pin "29") (pinfunction "29_29") (pintype "passive"))
      (node (ref "U2") (pin "E8") (pinfunction "IO,_(DATA6),_(DQ3T)/(DQ5T)_E8") (pintype "bidirectional"))
    )
    (net (code "21") (name "/CAM_IO") (class "Default")
      (node (ref "P2") (pin "16") (pinfunction "16_16") (pintype "passive"))
      (node (ref "P2") (pin "18") (pinfunction "18_18") (pintype "passive"))
      (node (ref "TP5") (pin "10") (pinfunction "10_10") (pintype "power_in"))
      (node (ref "TP5") (pin "9") (pinfunction "9_9") (pintype "power_in"))
    )
    (net (code "22") (name "/CAM_PCLK") (class "Default")
      (node (ref "P2") (pin "27") (pinfunction "27_27") (pintype "passive"))
      (node (ref "U2") (pin "A18") (pinfunction "IO,_(DQ5T)/(DQ5T)_A18") (pintype "bidirectional"))
    )
    (net (code "23") (name "/CAM_VS") (class "Default")
      (node (ref "P2") (pin "31") (pinfunction "31_31") (pintype "passive"))
      (node (ref "U2") (pin "D7") (pinfunction "IO,_VREFB8N2_D7") (pintype "bidirectional"))
    )
    (net (code "24") (name "/CMOS_OE") (class "Default")
      (node (ref "P2") (pin "12") (pinfunction "12_12") (pintype "passive"))
      (node (ref "TP5") (pin "12") (pinfunction "12_12") (pintype "power_in"))
      (node (ref "U2") (pin "U1") (pinfunction "IO,_DIFFIO_B1p_U1") (pintype "bidirectional"))
    )
    (net (code "25") (name "/CONF_DONE") (class "Default")
      (node (ref "R26") (pin "1") (pintype "passive"))
      (node (ref "U2") (pin "K14") (pinfunction "CONF_DONE_K14") (pintype "bidirectional"))
    )
    (net (code "26") (name "/DATA_CLK_OUTA") (class "Default")
      (node (ref "U2") (pin "U8") (pinfunction "IO,_DIFFIO_B27p,_(DQ3B)/(DQ5B)_U8") (pintype "bidirectional"))
    )
    (net (code "27") (name "/DATA_CLK_OUTB") (class "Default")
      (node (ref "U2") (pin "V8") (pinfunction "IO,_DIFFIO_B27n,_(DM5B/BWS#5B)/(DM5B0/BWS#5B0)_V8") (pintype "bidirectional"))
    )
    (net (code "28") (name "/DATA_CLK_OUT_A_N") (class "Default")
      (node (ref "J1") (pin "A5") (pinfunction "3-_A5") (pintype "passive"))
      (node (ref "R21") (pin "1") (pintype "passive"))
      (node (ref "U2") (pin "P11") (pinfunction "IO,_DIFFIO_B33n_P11") (pintype "bidirectional"))
    )
    (net (code "29") (name "/DATA_CLK_OUT_A_P") (class "Default")
      (node (ref "J1") (pin "A4") (pinfunction "3+_A4") (pintype "passive"))
      (node (ref "R21") (pin "2") (pintype "passive"))
      (node (ref "U2") (pin "P10") (pinfunction "IO,_DIFFIO_B33p,_(DQ5B)/(DQ5B)_P10") (pintype "bidirectional"))
    )
    (net (code "30") (name "/DATA_CLK_OUT_B_N") (class "Default")
      (node (ref "J1") (pin "D5") (pinfunction "3-_D5") (pintype "passive"))
      (node (ref "R23") (pin "1") (pintype "passive"))
      (node (ref "U2") (pin "V14") (pinfunction "IO,_DIFFIO_B34n,_(DQ5B)/(DQ5B)_V14") (pintype "bidirectional"))
    )
    (net (code "31") (name "/DATA_CLK_OUT_B_P") (class "Default")
      (node (ref "J1") (pin "D4") (pinfunction "3+_D4") (pintype "passive"))
      (node (ref "R23") (pin "2") (pintype "passive"))
      (node (ref "U2") (pin "U14") (pinfunction "IO,_DIFFIO_B34p,_(DQ5B)/(DQ5B)_U14") (pintype "bidirectional"))
    )
    (net (code "32") (name "/DATA_READY") (class "Default")
      (node (ref "U2") (pin "H16") (pinfunction "IO,_(DQS0R/CQ1R,DPCLK7)/(DQS0R/CQ1R,DPCLK7)_H16") (pintype "bidirectional"))
    )
    (net (code "33") (name "/DTP") (class "Default")
      (node (ref "J2") (pin "6") (pinfunction "TX-_6") (pintype "passive"))
      (node (ref "J3") (pin "6") (pinfunction "TX-_6") (pintype "passive"))
      (node (ref "TP1") (pin "6") (pinfunction "6_6") (pintype "power_in"))
      (node (ref "TP12") (pin "6") (pinfunction "6_6") (pintype "power_in"))
      (node (ref "U2") (pin "H1") (pinfunction "IO,_VREFB1N3_H1") (pintype "bidirectional"))
    )
    (net (code "34") (name "/EOSA") (class "Default")
      (node (ref "U2") (pin "D16") (pinfunction "IO,_DIFFIO_T49p,_(DQS0T/CQ1T,CDPCLK6)/(DQS0T/CQ1T,CDPCLK6)_D16") (pintype "bidirectional"))
    )
    (net (code "35") (name "/EOSB") (class "Default")
      (node (ref "U2") (pin "C16") (pinfunction "IO,_DIFFIO_T49n_C16") (pintype "bidirectional"))
    )
    (net (code "36") (name "/EOS_A") (class "Default")
      (node (ref "J2") (pin "5") (pintype "passive"))
      (node (ref "TP12") (pin "3") (pinfunction "3_3") (pintype "power_in"))
      (node (ref "U2") (pin "F18") (pinfunction "CLK5,_DIFFCLK_2n_F18") (pintype "input"))
    )
    (net (code "37") (name "/EOS_B") (class "Default")
      (node (ref "J3") (pin "5") (pintype "passive"))
      (node (ref "TP1") (pin "3") (pinfunction "3_3") (pintype "power_in"))
      (node (ref "U2") (pin "F17") (pinfunction "CLK4,_DIFFCLK_2p_F17") (pintype "input"))
    )
    (net (code "38") (name "/FRAME_CLK_OUTA") (class "Default")
      (node (ref "U2") (pin "V7") (pinfunction "IO,_DIFFIO_B26n,_(DQ3B)/(DQ5B)_V7") (pintype "bidirectional"))
    )
    (net (code "39") (name "/FRAME_CLK_OUTB") (class "Default")
      (node (ref "U2") (pin "U7") (pinfunction "IO,_DIFFIO_B26p_U7") (pintype "bidirectional"))
    )
    (net (code "40") (name "/FRAME_CLK_OUT_A_N") (class "Default")
      (node (ref "J1") (pin "A1") (pinfunction "1+_A1") (pintype "passive"))
      (node (ref "R22") (pin "1") (pintype "passive"))
      (node (ref "U2") (pin "V13") (pinfunction "IO,_DIFFIO_B32n,_(DQS4B/CQ5B,DPCLK4)/(DQS4B/CQ5B,DPCLK4)_V13") (pintype "bidirectional"))
    )
    (net (code "41") (name "/FRAME_CLK_OUT_A_P") (class "Default")
      (node (ref "J1") (pin "A2") (pinfunction "1-_A2") (pintype "passive"))
      (node (ref "R22") (pin "2") (pintype "passive"))
      (node (ref "U2") (pin "U13") (pinfunction "IO,_DIFFIO_B32p,_(DQ5B)/(DQ5B)_U13") (pintype "bidirectional"))
    )
    (net (code "42") (name "/FRAME_CLK_OUT_B_N") (class "Default")
      (node (ref "J1") (pin "D1") (pinfunction "1+_D1") (pintype "passive"))
      (node (ref "R24") (pin "1") (pintype "passive"))
      (node (ref "U2") (pin "V11") (pinfunction "IO,_DIFFIO_B28n_V11") (pintype "bidirectional"))
    )
    (net (code "43") (name "/FRAME_CLK_OUT_B_P") (class "Default")
      (node (ref "J1") (pin "D2") (pinfunction "1-_D2") (pintype "passive"))
      (node (ref "R24") (pin "2") (pintype "passive"))
      (node (ref "U2") (pin "U11") (pinfunction "IO,_DIFFIO_B28p,_(DQ5B)/(DQ5B)_U11") (pintype "bidirectional"))
    )
    (net (code "44") (name "/Hs") (class "Default")
      (node (ref "U2") (pin "A7") (pinfunction "IO,_DIFFIO_T19n,_(PADD18),_(DQ3T)/(DQ5T)_A7") (pintype "bidirectional"))
    )
    (net (code "45") (name "/IO1") (class "Default")
      (node (ref "TP8") (pin "1") (pinfunction "TP_1") (pintype "passive"))
      (node (ref "U2") (pin "N1") (pinfunction "CLK3,_DIFFCLK_1n_N1") (pintype "input"))
      (node (ref "U5") (pin "27") (pinfunction "I/O[0]_27") (pintype "bidirectional"))
    )
    (net (code "46") (name "/IO2") (class "Default")
      (node (ref "TP11") (pin "1") (pinfunction "TP_1") (pintype "passive"))
      (node (ref "U2") (pin "V9") (pinfunction "CLK14,_DIFFCLK_6n_V9") (pintype "input"))
      (node (ref "U5") (pin "28") (pinfunction "I/O[1]_28") (pintype "bidirectional"))
    )
    (net (code "47") (name "/IO3") (class "Default")
      (node (ref "TP7") (pin "1") (pinfunction "TP_1") (pintype "passive"))
      (node (ref "U2") (pin "B9") (pinfunction "CLK11,_DIFFCLK_4p_B9") (pintype "input"))
      (node (ref "U5") (pin "2") (pinfunction "I/O[2]_2") (pintype "bidirectional"))
    )
    (net (code "48") (name "/IO4") (class "Default")
      (node (ref "TP10") (pin "1") (pinfunction "TP_1") (pintype "passive"))
      (node (ref "U2") (pin "A4") (pinfunction "IO,_(DATA7),_(DQ3T)/(DQ5T)_A4") (pintype "bidirectional"))
      (node (ref "U5") (pin "3") (pinfunction "I/O[3]_3") (pintype "bidirectional"))
    )
    (net (code "49") (name "/IO5") (class "Default")
      (node (ref "TP6") (pin "1") (pinfunction "TP_1") (pintype "passive"))
      (node (ref "U2") (pin "E7") (pinfunction "IO,_(DATA9),_(DQ3T)/(DQ5T)_E7") (pintype "bidirectional"))
      (node (ref "U5") (pin "5") (pinfunction "I/O[4]_5") (pintype "bidirectional"))
    )
    (net (code "50") (name "/IO6") (class "Default")
      (node (ref "TP9") (pin "1") (pinfunction "TP_1") (pintype "passive"))
      (node (ref "U2") (pin "B6") (pinfunction "IO,_DIFFIO_T18p,_(DATA15)_B6") (pintype "bidirectional"))
      (node (ref "U5") (pin "6") (pinfunction "I/O[5]_6") (pintype "bidirectional"))
    )
    (net (code "51") (name "/IO7") (class "Default")
      (node (ref "TP1") (pin "1") (pinfunction "1_1") (pintype "power_in"))
      (node (ref "U2") (pin "U3") (pinfunction "IO,_DIFFIO_B16p,_(DQS3B/CQ3B#,DPCLK2)/(DQS3B/CQ3B#,DPCLK2)_U3") (pintype "bidirectional"))
      (node (ref "U5") (pin "8") (pinfunction "I/O[6]_8") (pintype "bidirectional"))
    )
    (net (code "52") (name "/IO8") (class "Default")
      (node (ref "U2") (pin "B8") (pinfunction "IO,_DIFFIO_T20p,_(DATA3)_B8") (pintype "bidirectional"))
      (node (ref "U5") (pin "9") (pinfunction "I/O[7]_9") (pintype "bidirectional"))
    )
    (net (code "53") (name "/IO9") (class "Default")
      (node (ref "TP1") (pin "2") (pinfunction "2_2") (pintype "power_in"))
      (node (ref "U2") (pin "B12") (pinfunction "IO,_DIFFIO_T31p,_(PADD10)_B12") (pintype "bidirectional"))
      (node (ref "U5") (pin "13") (pinfunction "I/O[8]_13") (pintype "bidirectional"))
    )
    (net (code "54") (name "/IO10") (class "Default")
      (node (ref "U2") (pin "B14") (pinfunction "IO,_DIFFIO_T36p,_(PADD6),_(DQ5T)/(DQ5T)_B14") (pintype "bidirectional"))
      (node (ref "U5") (pin "14") (pinfunction "I/O[9]_14") (pintype "bidirectional"))
    )
    (net (code "55") (name "/IO11") (class "Default")
      (node (ref "U2") (pin "A8") (pinfunction "IO,_DIFFIO_T20n,_(DATA2),_(DQ3T)/(DQ5T)_A8") (pintype "bidirectional"))
      (node (ref "U5") (pin "16") (pinfunction "I/O[10]_16") (pintype "bidirectional"))
    )
    (net (code "56") (name "/IO12") (class "Default")
      (node (ref "U2") (pin "E6") (pinfunction "IO,_VREFB8N3_E6") (pintype "bidirectional"))
      (node (ref "U5") (pin "17") (pinfunction "I/O[11]_17") (pintype "bidirectional"))
    )
    (net (code "57") (name "/IO13") (class "Default")
      (node (ref "U2") (pin "V4") (pinfunction "IO,_DIFFIO_B17n,_(DQ3B)/(DQ5B)_V4") (pintype "bidirectional"))
      (node (ref "U5") (pin "19") (pinfunction "I/O[12]_19") (pintype "bidirectional"))
    )
    (net (code "58") (name "/IO14") (class "Default")
      (node (ref "U2") (pin "B4") (pinfunction "IO,_(DATA8)_B4") (pintype "bidirectional"))
      (node (ref "U5") (pin "20") (pinfunction "I/O[13]_20") (pintype "bidirectional"))
    )
    (net (code "59") (name "/IO15") (class "Default")
      (node (ref "U2") (pin "E9") (pinfunction "IO,_VREFB8N0_E9") (pintype "bidirectional"))
      (node (ref "U5") (pin "22") (pinfunction "I/O[14]_22") (pintype "bidirectional"))
    )
    (net (code "60") (name "/IO16") (class "Default")
      (node (ref "U2") (pin "P6") (pinfunction "IO,_(DQS1B/CQ1B#,CDPCLK2)/(DQS1B/CQ1B#,CDPCLK2)_P6") (pintype "bidirectional"))
      (node (ref "U5") (pin "23") (pinfunction "I/O[15]_23") (pintype "bidirectional"))
    )
    (net (code "61") (name "/IO_5") (class "Default")
      (node (ref "U2") (pin "B3") (pinfunction "IO,_DIFFIO_T4p,_(DATA11)_B3") (pintype "bidirectional"))
    )
    (net (code "62") (name "/IO_6") (class "Default")
      (node (ref "U2") (pin "C7") (pinfunction "IO,_VREFB8N1_C7") (pintype "bidirectional"))
    )
    (net (code "63") (name "/IO_7") (class "Default")
      (node (ref "U2") (pin "P7") (pinfunction "IO,_VREFB3N1_P7") (pintype "bidirectional"))
    )
    (net (code "64") (name "/IO_8") (class "Default")
      (node (ref "U2") (pin "A6") (pinfunction "IO,_DIFFIO_T18n,_(PADD19),_(DQ3T)/(DQ5T)_A6") (pintype "bidirectional"))
    )
    (net (code "65") (name "/IO_9") (class "Default")
      (node (ref "U2") (pin "A11") (pinfunction "IO,_DIFFIO_T29n,_(PADD11),_(DQ5T)/(DQ5T)_A11") (pintype "bidirectional"))
    )
    (net (code "66") (name "/IO_10") (class "Default")
      (node (ref "U2") (pin "A13") (pinfunction "IO,_DIFFIO_T35n,_(PADD7)_A13") (pintype "bidirectional"))
    )
    (net (code "67") (name "/IO_11") (class "Default")
      (node (ref "U2") (pin "P1") (pinfunction "IO,_DIFFIO_L44n,_(DQ3L)/(DQ1L)_P1") (pintype "bidirectional"))
    )
    (net (code "68") (name "/IO_12") (class "Default")
      (node (ref "U2") (pin "D5") (pinfunction "IO,_(DATA12),_(DQS1T/CQ1T#,CDPCLK7)/(DQS1T/CQ1T#,CDPCLK7)_D5") (pintype "bidirectional"))
    )
    (net (code "69") (name "/IO_13") (class "Default")
      (node (ref "U2") (pin "U4") (pinfunction "IO,_DIFFIO_B17p,_(DQ3B)/(DQ5B)_U4") (pintype "bidirectional"))
    )
    (net (code "70") (name "/IO_14") (class "Default")
      (node (ref "U2") (pin "M3") (pinfunction "IO,_VREFB2N1_M3") (pintype "bidirectional"))
    )
    (net (code "71") (name "/IO_15") (class "Default")
      (node (ref "U2") (pin "D9") (pinfunction "IO,_DIFFIO_T24p,_(PADD17),_(DQS5T/CQ5T#,DPCLK10)/(DQS5T/CQ5T#,DPCLK10)_D9") (pintype "bidirectional"))
    )
    (net (code "72") (name "/IO_16") (class "Default")
      (node (ref "U2") (pin "T4") (pinfunction "IO,_VREFB3N3_T4") (pintype "bidirectional"))
    )
    (net (code "73") (name "/LVDS_CHANNEL_1_N") (class "Default")
      (node (ref "J1") (pin "B2") (pinfunction "1-_B2") (pintype "passive"))
      (node (ref "R20") (pin "1") (pintype "passive"))
      (node (ref "U2") (pin "M14") (pinfunction "IO,_DIFFIO_R38n,_(DQ3R)/(DQ1R)_M14") (pintype "bidirectional"))
    )
    (net (code "74") (name "/LVDS_CHANNEL_1_P") (class "Default")
      (node (ref "J1") (pin "B1") (pinfunction "1+_B1") (pintype "passive"))
      (node (ref "R20") (pin "2") (pintype "passive"))
      (node (ref "U2") (pin "L13") (pinfunction "IO,_DIFFIO_R38p,_(DQ3R)/(DQ1R)_L13") (pintype "bidirectional"))
    )
    (net (code "75") (name "/LVDS_CHANNEL_2_N") (class "Default")
      (node (ref "J1") (pin "B6") (pinfunction "2-_B6") (pintype "passive"))
      (node (ref "R19") (pin "1") (pintype "passive"))
      (node (ref "U2") (pin "L15") (pinfunction "IO,_DIFFIO_R36n,_(DQ3R)/(DQ1R)_L15") (pintype "bidirectional"))
    )
    (net (code "76") (name "/LVDS_CHANNEL_2_P") (class "Default")
      (node (ref "J1") (pin "B3") (pinfunction "2+_B3") (pintype "passive"))
      (node (ref "R19") (pin "2") (pintype "passive"))
      (node (ref "U2") (pin "L14") (pinfunction "IO,_DIFFIO_R36p,_(DQ3R)/(DQ1R)_L14") (pintype "bidirectional"))
    )
    (net (code "77") (name "/LVDS_CHANNEL_3_N") (class "Default")
      (node (ref "J1") (pin "B4") (pinfunction "3+_B4") (pintype "passive"))
      (node (ref "R17") (pin "1") (pintype "passive"))
      (node (ref "U2") (pin "M17") (pinfunction "IO,_DIFFIO_R33n,_(DQ3R)/(DQ1R)_M17") (pintype "bidirectional"))
    )
    (net (code "78") (name "/LVDS_CHANNEL_3_P") (class "Default")
      (node (ref "J1") (pin "B5") (pinfunction "3-_B5") (pintype "passive"))
      (node (ref "R17") (pin "2") (pintype "passive"))
      (node (ref "U2") (pin "L16") (pinfunction "IO,_DIFFIO_R33p,_(DQS1R/CQ1R#,DPCLK6)/(DQS1R/CQ1R#,DPCLK6)_L16") (pintype "bidirectional"))
    )
    (net (code "79") (name "/LVDS_CHANNEL_4_N") (class "Default")
      (node (ref "J1") (pin "B7") (pinfunction "4+_B7") (pintype "passive"))
      (node (ref "R18") (pin "1") (pintype "passive"))
      (node (ref "U2") (pin "M18") (pinfunction "IO,_DIFFIO_R32n,_(DEV_OE)_M18") (pintype "bidirectional"))
    )
    (net (code "80") (name "/LVDS_CHANNEL_4_P") (class "Default")
      (node (ref "J1") (pin "B8") (pinfunction "4-_B8") (pintype "passive"))
      (node (ref "R18") (pin "2") (pintype "passive"))
      (node (ref "U2") (pin "L17") (pinfunction "IO,_DIFFIO_R32p,_(DEV_CLRn)_L17") (pintype "bidirectional"))
    )
    (net (code "81") (name "/LVDS_CHANNEL_5_N") (class "Default")
      (node (ref "J1") (pin "C2") (pinfunction "1-_C2") (pintype "passive"))
      (node (ref "R16") (pin "2") (pintype "passive"))
      (node (ref "U2") (pin "K18") (pinfunction "IO,_DIFFIO_R29n,_(DM1R/BWS#1R)/(DM1R0/BWS#1R0)_K18") (pintype "bidirectional"))
    )
    (net (code "82") (name "/LVDS_CHANNEL_5_P") (class "Default")
      (node (ref "J1") (pin "C1") (pinfunction "1+_C1") (pintype "passive"))
      (node (ref "R16") (pin "1") (pintype "passive"))
      (node (ref "U2") (pin "K17") (pinfunction "IO,_DIFFIO_R29p,_(DQ1R)/(DQ1R)_K17") (pintype "bidirectional"))
    )
    (net (code "83") (name "/LVDS_CHANNEL_6_N") (class "Default")
      (node (ref "J1") (pin "C6") (pinfunction "2-_C6") (pintype "passive"))
      (node (ref "R15") (pin "1") (pintype "passive"))
      (node (ref "U2") (pin "H14") (pinfunction "IO,_DIFFIO_R8n,_(nAVD),_(DQ1R)/(DQ1R)_H14") (pintype "bidirectional"))
    )
    (net (code "84") (name "/LVDS_CHANNEL_6_P") (class "Default")
      (node (ref "J1") (pin "C3") (pinfunction "2+_C3") (pintype "passive"))
      (node (ref "R15") (pin "2") (pintype "passive"))
      (node (ref "U2") (pin "H13") (pinfunction "IO,_DIFFIO_R8p,_(RDY),_(DQ1R)/(DQ1R)_H13") (pintype "bidirectional"))
    )
    (net (code "85") (name "/LVDS_CHANNEL_7_N") (class "Default")
      (node (ref "J1") (pin "C4") (pinfunction "3+_C4") (pintype "passive"))
      (node (ref "R14") (pin "1") (pintype "passive"))
      (node (ref "U2") (pin "G18") (pinfunction "IO,_DIFFIO_R27n,_(INIT_DONE)_G18") (pintype "bidirectional"))
    )
    (net (code "86") (name "/LVDS_CHANNEL_7_P") (class "Default")
      (node (ref "J1") (pin "C5") (pinfunction "3-_C5") (pintype "passive"))
      (node (ref "R14") (pin "2") (pintype "passive"))
      (node (ref "U2") (pin "G17") (pinfunction "IO,_DIFFIO_R27p,_(CRC_ERROR)_G17") (pintype "bidirectional"))
    )
    (net (code "87") (name "/LVDS_CHANNEL_8_N") (class "Default")
      (node (ref "J1") (pin "C7") (pinfunction "4+_C7") (pintype "passive"))
      (node (ref "R13") (pin "1") (pintype "passive"))
      (node (ref "U2") (pin "D18") (pinfunction "IO,_DIFFIO_R12n,_(nWE),_(DQ1R)/(DQ1R)_D18") (pintype "bidirectional"))
    )
    (net (code "88") (name "/LVDS_CHANNEL_8_P") (class "Default")
      (node (ref "J1") (pin "C8") (pinfunction "4-_C8") (pintype "passive"))
      (node (ref "R13") (pin "2") (pintype "passive"))
      (node (ref "U2") (pin "D17") (pinfunction "IO,_DIFFIO_R12p,_(nOE),_(DQ1R)/(DQ1R)_D17") (pintype "bidirectional"))
    )
    (net (code "89") (name "/NRESET") (class "Default")
      (node (ref "R34") (pin "1") (pintype "passive"))
      (node (ref "U5") (pin "24") (pinfunction "NRESET_24") (pintype "input"))
    )
    (net (code "90") (name "/NetL1_2") (class "Default")
      (node (ref "C20") (pin "2") (pinfunction "2_2") (pintype "passive"))
      (node (ref "C50") (pin "1") (pinfunction "1_1") (pintype "passive"))
      (node (ref "L2") (pin "2") (pinfunction "2_2") (pintype "passive"))
      (node (ref "U2") (pin "E15") (pinfunction "VCCD_PLL2_E15") (pintype "power_in"))
      (node (ref "U2") (pin "F5") (pinfunction "VCCD_PLL3_F5") (pintype "power_in"))
      (node (ref "U2") (pin "P15") (pinfunction "VCCD_PLL4_P15") (pintype "power_in"))
      (node (ref "U2") (pin "P4") (pinfunction "VCCD_PLL1_P4") (pintype "power_in"))
    )
    (net (code "91") (name "/PDWN") (class "Default")
      (node (ref "J2") (pin "2") (pinfunction "RX-_2") (pintype "passive"))
      (node (ref "J3") (pin "2") (pinfunction "RX-_2") (pintype "passive"))
      (node (ref "TP1") (pin "5") (pinfunction "5_5") (pintype "power_in"))
      (node (ref "TP12") (pin "5") (pinfunction "5_5") (pintype "power_in"))
      (node (ref "U2") (pin "C2") (pinfunction "IO,_VREFB1N0_C2") (pintype "bidirectional"))
    )
    (net (code "92") (name "/PLL_LOCK_A") (class "Default")
      (node (ref "J2") (pin "3") (pinfunction "TX+_3") (pintype "passive"))
      (node (ref "TP12") (pin "4") (pinfunction "4_4") (pintype "power_in"))
      (node (ref "U2") (pin "D2") (pinfunction "IO,_DIFFIO_L8p,_(DQ1L)/(DQ1L)_D2") (pintype "bidirectional"))
    )
    (net (code "93") (name "/PLL_LOCK_B") (class "Default")
      (node (ref "J3") (pin "3") (pinfunction "TX+_3") (pintype "passive"))
      (node (ref "TP1") (pin "4") (pinfunction "4_4") (pintype "power_in"))
      (node (ref "U2") (pin "N15") (pinfunction "IO,_(DM3R/BWS#3R)/(DM1R1/BWS#1R1)_N15") (pintype "bidirectional"))
    )
    (net (code "94") (name "/SCL") (class "Default")
      (node (ref "P2") (pin "8") (pinfunction "8_8") (pintype "passive"))
      (node (ref "R8") (pin "1") (pintype "passive"))
      (node (ref "TP5") (pin "14") (pinfunction "14_14") (pintype "power_in"))
      (node (ref "U5") (pin "26") (pinfunction "SCL_26") (pintype "input"))
    )
    (net (code "95") (name "/SDA") (class "Default")
      (node (ref "P2") (pin "6") (pinfunction "6_6") (pintype "passive"))
      (node (ref "R9") (pin "2") (pintype "passive"))
      (node (ref "TP5") (pin "15") (pinfunction "15_15") (pintype "power_in"))
      (node (ref "U5") (pin "25") (pinfunction "SDA_25") (pintype "bidirectional"))
    )
    (net (code "96") (name "/START_A_N") (class "Default")
      (node (ref "J1") (pin "A7") (pinfunction "4+_A7") (pintype "passive"))
      (node (ref "U2") (pin "B1") (pinfunction "IO,_DIFFIO_L1n_B1") (pintype "bidirectional"))
    )
    (net (code "97") (name "/START_A_P") (class "Default")
      (node (ref "J1") (pin "A8") (pinfunction "4-_A8") (pintype "passive"))
      (node (ref "U2") (pin "B2") (pinfunction "IO,_DIFFIO_L1p,_(DQ1L)/(DQ1L)_B2") (pintype "bidirectional"))
    )
    (net (code "98") (name "/START_B_N") (class "Default")
      (node (ref "J1") (pin "D7") (pinfunction "4+_D7") (pintype "passive"))
      (node (ref "U2") (pin "G1") (pinfunction "IO,_DIFFIO_L20n,_(DQ1L)/(DQ1L)_G1") (pintype "bidirectional"))
    )
    (net (code "99") (name "/START_B_P") (class "Default")
      (node (ref "J1") (pin "D8") (pinfunction "4-_D8") (pintype "passive"))
      (node (ref "U2") (pin "G2") (pinfunction "IO,_DIFFIO_L20p,_(DQ1L)/(DQ1L)_G2") (pintype "bidirectional"))
    )
    (net (code "100") (name "/SYS_CLK1_N") (class "Default")
      (node (ref "J1") (pin "A3") (pinfunction "2+_A3") (pintype "passive"))
      (node (ref "U2") (pin "P18") (pinfunction "IO,_DIFFIO_R42n,_(DQ3R)/(DQ1R)_P18") (pintype "bidirectional"))
    )
    (net (code "101") (name "/SYS_CLK1_P") (class "Default")
      (node (ref "J1") (pin "A6") (pinfunction "2-_A6") (pintype "passive"))
      (node (ref "U2") (pin "P17") (pinfunction "IO,_DIFFIO_R42p,_(DQ3R)/(DQ1R)_P17") (pintype "bidirectional"))
    )
    (net (code "102") (name "/SYS_CLK2_N") (class "Default")
      (node (ref "J1") (pin "D3") (pinfunction "2+_D3") (pintype "passive"))
      (node (ref "U2") (pin "C18") (pinfunction "IO,_DIFFIO_R5n,_(PADD22),_(DQ1R)/(DQ1R)_C18") (pintype "bidirectional"))
    )
    (net (code "103") (name "/SYS_CLK2_P") (class "Default")
      (node (ref "J1") (pin "D6") (pinfunction "2-_D6") (pintype "passive"))
      (node (ref "U2") (pin "C17") (pinfunction "IO,_DIFFIO_R5p,_(PADD21),_(DQ1R)/(DQ1R)_C17") (pintype "bidirectional"))
    )
    (net (code "104") (name "/T18") (class "Default")
      (node (ref "J2") (pin "4") (pintype "passive"))
      (node (ref "J3") (pin "4") (pintype "passive"))
      (node (ref "TP12") (pin "2") (pinfunction "2_2") (pintype "power_in"))
      (node (ref "U2") (pin "T18") (pinfunction "IO,_(DQS3R/CQ3R#,CDPCLK4)/(DQS3R/CQ3R#,CDPCLK4)_T18") (pintype "bidirectional"))
    )
    (net (code "105") (name "/TCK") (class "Default")
      (node (ref "P1") (pin "1") (pinfunction "1_1") (pintype "passive"))
      (node (ref "R10") (pin "2") (pinfunction "2_2") (pintype "passive"))
      (node (ref "U2") (pin "J1") (pinfunction "TCK_J1") (pintype "input"))
    )
    (net (code "106") (name "/TDI") (class "Default")
      (node (ref "P1") (pin "9") (pinfunction "9_9") (pintype "passive"))
      (node (ref "R12") (pin "2") (pinfunction "2_2") (pintype "passive"))
      (node (ref "U2") (pin "J6") (pinfunction "TDI_J6") (pintype "input"))
    )
    (net (code "107") (name "/TDO") (class "Default")
      (node (ref "P1") (pin "3") (pinfunction "3_3") (pintype "passive"))
      (node (ref "U2") (pin "J5") (pinfunction "TDO_J5") (pintype "output"))
    )
    (net (code "108") (name "/TMS") (class "Default")
      (node (ref "P1") (pin "5") (pinfunction "5_5") (pintype "passive"))
      (node (ref "R11") (pin "2") (pinfunction "2_2") (pintype "passive"))
      (node (ref "U2") (pin "J2") (pinfunction "TMS_J2") (pintype "input"))
    )
    (net (code "109") (name "/V17") (class "Default")
      (node (ref "J2") (pin "1") (pinfunction "RX+_1") (pintype "passive"))
      (node (ref "J3") (pin "1") (pinfunction "RX+_1") (pintype "passive"))
      (node (ref "TP12") (pin "1") (pinfunction "1_1") (pintype "power_in"))
      (node (ref "U2") (pin "V17") (pinfunction "IO,_DIFFIO_B47n_V17") (pintype "bidirectional"))
    )
    (net (code "110") (name "/Vs") (class "Default")
      (node (ref "U2") (pin "A3") (pinfunction "IO,_DIFFIO_T4n,_(DATA10),_(DM3T/BWS#3T)/(DM5T1/BWS#5T1)_A3") (pintype "bidirectional"))
    )
    (net (code "111") (name "/nSTATUS") (class "Default")
      (node (ref "R25") (pin "1") (pintype "passive"))
      (node (ref "U2") (pin "G5") (pinfunction "nSTATUS_G5") (pintype "bidirectional"))
    )
    (net (code "112") (name "1V8") (class "Default")
      (node (ref "C13") (pin "1") (pinfunction "1_1") (pintype "passive"))
      (node (ref "C14") (pin "1") (pinfunction "1_1") (pintype "passive"))
      (node (ref "C15") (pin "1") (pinfunction "1_1") (pintype "passive"))
      (node (ref "C16") (pin "2") (pinfunction "2_2") (pintype "passive"))
      (node (ref "C17") (pin "1") (pinfunction "1_1") (pintype "passive"))
      (node (ref "C18") (pin "2") (pinfunction "2_2") (pintype "passive"))
      (node (ref "C19") (pin "1") (pinfunction "1_1") (pintype "passive"))
      (node (ref "C49") (pin "1") (pinfunction "1_1") (pintype "passive"))
      (node (ref "C52") (pin "1") (pinfunction "1_1") (pintype "passive"))
      (node (ref "C53") (pin "1") (pinfunction "1_1") (pintype "passive"))
      (node (ref "C54") (pin "1") (pinfunction "1_1") (pintype "passive"))
      (node (ref "C55") (pin "1") (pinfunction "1_1") (pintype "passive"))
      (node (ref "C56") (pin "1") (pinfunction "1_1") (pintype "passive"))
      (node (ref "Q1") (pin "1") (pinfunction "G_1") (pintype "passive"))
      (node (ref "Q2") (pin "1") (pinfunction "G_1") (pintype "passive"))
      (node (ref "R31") (pin "1") (pintype "passive"))
      (node (ref "R33") (pin "1") (pintype "passive"))
      (node (ref "R34") (pin "2") (pintype "passive"))
      (node (ref "R8") (pin "2") (pintype "passive"))
      (node (ref "R9") (pin "1") (pintype "passive"))
      (node (ref "Test Point 1") (pin "1") (pinfunction "1_1") (pintype "passive"))
      (node (ref "U2") (pin "D11") (pinfunction "VCCIO7_D11") (pintype "power_in"))
      (node (ref "U2") (pin "D13") (pinfunction "VCCIO7_D13") (pintype "power_in"))
      (node (ref "U2") (pin "D15") (pinfunction "VCCIO7_D15") (pintype "power_in"))
      (node (ref "U2") (pin "D4") (pinfunction "VCCIO8_D4") (pintype "power_in"))
      (node (ref "U2") (pin "D6") (pinfunction "VCCIO8_D6") (pintype "power_in"))
      (node (ref "U2") (pin "D8") (pinfunction "VCCIO8_D8") (pintype "power_in"))
      (node (ref "U2") (pin "R6") (pinfunction "VCCIO3_R6") (pintype "power_in"))
      (node (ref "U2") (pin "R7") (pinfunction "VCCIO3_R7") (pintype "power_in"))
      (node (ref "U2") (pin "R9") (pinfunction "VCCIO3_R9") (pintype "power_in"))
      (node (ref "U5") (pin "12") (pinfunction "VDDM_12") (pintype "power_in"))
      (node (ref "U5") (pin "18") (pinfunction "VCC2_18") (pintype "power_in"))
      (node (ref "U5") (pin "4") (pinfunction "VCC1_4") (pintype "power_in"))
    )
    (net (code "113") (name "2V5_VCCA") (class "Default")
      (node (ref "L1") (pin "1") (pinfunction "1_1") (pintype "passive"))
      (node (ref "P1") (pin "4") (pinfunction "4_4") (pintype "passive"))
      (node (ref "R11") (pin "1") (pinfunction "1_1") (pintype "passive"))
      (node (ref "R12") (pin "1") (pinfunction "1_1") (pintype "passive"))
      (node (ref "Test Point 13") (pin "1") (pinfunction "1_1") (pintype "passive"))
    )
    (net (code "114") (name "5V0") (class "Default")
      (node (ref "J4") (pin "2") (pinfunction "5V_2") (pintype "passive"))
      (node (ref "J5") (pin "2") (pinfunction "5V_2") (pintype "passive"))
      (node (ref "P2") (pin "24") (pinfunction "24_24") (pintype "passive"))
      (node (ref "P2") (pin "25") (pinfunction "25_25") (pintype "passive"))
      (node (ref "P2") (pin "26") (pinfunction "26_26") (pintype "passive"))
      (node (ref "R30") (pin "1") (pintype "passive"))
      (node (ref "R32") (pin "1") (pintype "passive"))
      (node (ref "TP5") (pin "5") (pinfunction "5_5") (pintype "power_in"))
      (node (ref "TP5") (pin "6") (pinfunction "6_6") (pintype "power_in"))
      (node (ref "Test Point 10") (pin "1") (pinfunction "1_1") (pintype "passive"))
    )
    (net (code "115") (name "AGND") (class "Default")
      (node (ref "C26") (pin "2") (pinfunction "2_2") (pintype "passive"))
      (node (ref "C48") (pin "2") (pinfunction "2_2") (pintype "passive"))
      (node (ref "R27") (pin "1") (pinfunction "1_1") (pintype "passive"))
      (node (ref "Test Point 14") (pin "1") (pinfunction "1_1") (pintype "passive"))
      (node (ref "U2") (pin "E5") (pinfunction "GNDA3_E5") (pintype "power_in"))
      (node (ref "U2") (pin "F15") (pinfunction "GNDA2_F15") (pintype "power_in"))
      (node (ref "U2") (pin "P14") (pinfunction "GNDA4_P14") (pintype "power_in"))
      (node (ref "U2") (pin "P5") (pinfunction "GNDA1_P5") (pintype "power_in"))
    )
    (net (code "116") (name "GND") (class "Default")
      (node (ref "C13") (pin "2") (pinfunction "2_2") (pintype "passive"))
      (node (ref "C14") (pin "2") (pinfunction "2_2") (pintype "passive"))
      (node (ref "C15") (pin "2") (pinfunction "2_2") (pintype "passive"))
      (node (ref "C16") (pin "1") (pinfunction "1_1") (pintype "passive"))
      (node (ref "C17") (pin "2") (pinfunction "2_2") (pintype "passive"))
      (node (ref "C18") (pin "1") (pinfunction "1_1") (pintype "passive"))
      (node (ref "C19") (pin "2") (pinfunction "2_2") (pintype "passive"))
      (node (ref "C20") (pin "1") (pinfunction "1_1") (pintype "passive"))
      (node (ref "C21") (pin "2") (pinfunction "2_2") (pintype "passive"))
      (node (ref "C22") (pin "2") (pinfunction "2_2") (pintype "passive"))
      (node (ref "C23") (pin "1") (pinfunction "1_1") (pintype "passive"))
      (node (ref "C24") (pin "2") (pinfunction "2_2") (pintype "passive"))
      (node (ref "C25") (pin "2") (pinfunction "2_2") (pintype "passive"))
      (node (ref "C27") (pin "2") (pinfunction "2_2") (pintype "passive"))
      (node (ref "C28") (pin "1") (pinfunction "1_1") (pintype "passive"))
      (node (ref "C29") (pin "2") (pinfunction "2_2") (pintype "passive"))
      (node (ref "C30") (pin "1") (pinfunction "1_1") (pintype "passive"))
      (node (ref "C31") (pin "1") (pinfunction "1_1") (pintype "passive"))
      (node (ref "C32") (pin "1") (pinfunction "1_1") (pintype "passive"))
      (node (ref "C33") (pin "1") (pinfunction "1_1") (pintype "passive"))
      (node (ref "C34") (pin "2") (pinfunction "2_2") (pintype "passive"))
      (node (ref "C35") (pin "2") (pinfunction "2_2") (pintype "passive"))
      (node (ref "C36") (pin "2") (pinfunction "2_2") (pintype "passive"))
      (node (ref "C37") (pin "1") (pinfunction "1_1") (pintype "passive"))
      (node (ref "C38") (pin "2") (pinfunction "2_2") (pintype "passive"))
      (node (ref "C39") (pin "2") (pinfunction "2_2") (pintype "passive"))
      (node (ref "C40") (pin "1") (pinfunction "1_1") (pintype "passive"))
      (node (ref "C41") (pin "2") (pinfunction "2_2") (pintype "passive"))
      (node (ref "C42") (pin "2") (pinfunction "2_2") (pintype "passive"))
      (node (ref "C43") (pin "2") (pinfunction "2_2") (pintype "passive"))
      (node (ref "C44") (pin "2") (pinfunction "2_2") (pintype "passive"))
      (node (ref "C45") (pin "1") (pinfunction "1_1") (pintype "passive"))
      (node (ref "C46") (pin "2") (pinfunction "2_2") (pintype "passive"))
      (node (ref "C47") (pin "2") (pinfunction "2_2") (pintype "passive"))
      (node (ref "C49") (pin "2") (pinfunction "2_2") (pintype "passive"))
      (node (ref "C50") (pin "2") (pinfunction "2_2") (pintype "passive"))
      (node (ref "C51") (pin "1") (pinfunction "1_1") (pintype "passive"))
      (node (ref "C52") (pin "2") (pinfunction "2_2") (pintype "passive"))
      (node (ref "C53") (pin "2") (pinfunction "2_2") (pintype "passive"))
      (node (ref "C54") (pin "2") (pinfunction "2_2") (pintype "passive"))
      (node (ref "C55") (pin "2") (pinfunction "2_2") (pintype "passive"))
      (node (ref "C56") (pin "2") (pinfunction "2_2") (pintype "passive"))
      (node (ref "J4") (pin "3") (pinfunction "COMMON_3") (pintype "passive"))
      (node (ref "J4") (pin "7") (pinfunction "COMMON_7") (pintype "passive"))
      (node (ref "J5") (pin "3") (pinfunction "COMMON_3") (pintype "passive"))
      (node (ref "J5") (pin "7") (pinfunction "COMMON_7") (pintype "passive"))
      (node (ref "P1") (pin "10") (pinfunction "10_10") (pintype "passive"))
      (node (ref "P1") (pin "2") (pinfunction "2_2") (pintype "passive"))
      (node (ref "P2") (pin "14") (pinfunction "14_14") (pintype "passive"))
      (node (ref "P2") (pin "20") (pinfunction "20_20") (pintype "passive"))
      (node (ref "P2") (pin "22") (pinfunction "22_22") (pintype "passive"))
      (node (ref "P2") (pin "28") (pinfunction "28_28") (pintype "passive"))
      (node (ref "P2") (pin "33") (pinfunction "33_33") (pintype "passive"))
      (node (ref "P2") (pin "34") (pinfunction "34_34") (pintype "passive"))
      (node (ref "P2") (pin "4") (pinfunction "4_4") (pintype "passive"))
      (node (ref "R10") (pin "1") (pinfunction "1_1") (pintype "passive"))
      (node (ref "R27") (pin "2") (pinfunction "2_2") (pintype "passive"))
      (node (ref "TP5") (pin "1") (pinfunction "1_1") (pintype "power_in"))
      (node (ref "TP5") (pin "11") (pinfunction "11_11") (pintype "power_in"))
      (node (ref "TP5") (pin "16") (pinfunction "16_16") (pintype "power_in"))
      (node (ref "TP5") (pin "4") (pinfunction "4_4") (pintype "power_in"))
      (node (ref "TP5") (pin "7") (pinfunction "7_7") (pintype "power_in"))
      (node (ref "TP5") (pin "8") (pinfunction "8_8") (pintype "power_in"))
      (node (ref "Test Point 12") (pin "1") (pinfunction "1_1") (pintype "passive"))
      (node (ref "Test Point 7") (pin "1") (pinfunction "1_1") (pintype "passive"))
      (node (ref "Test Point 9") (pin "1") (pinfunction "1_1") (pintype "passive"))
      (node (ref "U2") (pin "A10") (pinfunction "CLK8,_DIFFCLK_5n_A10") (pintype "input"))
      (node (ref "U2") (pin "A2") (pinfunction "IO,_PLL3_CLKOUTp_A2") (pintype "bidirectional"))
      (node (ref "U2") (pin "B10") (pinfunction "CLK9,_DIFFCLK_5p_B10") (pintype "input"))
      (node (ref "U2") (pin "B17") (pinfunction "IO,_VREFB6N0_B17") (pintype "bidirectional"))
      (node (ref "U2") (pin "C11") (pinfunction "GND_C11") (pintype "power_in"))
      (node (ref "U2") (pin "C12") (pinfunction "IO,_VREFB7N2_C12") (pintype "bidirectional"))
      (node (ref "U2") (pin "C13") (pinfunction "GND_C13") (pintype "power_in"))
      (node (ref "U2") (pin "C15") (pinfunction "GND_C15") (pintype "power_in"))
      (node (ref "U2") (pin "C4") (pinfunction "GND_C4") (pintype "power_in"))
      (node (ref "U2") (pin "C6") (pinfunction "GND_C6") (pintype "power_in"))
      (node (ref "U2") (pin "C8") (pinfunction "GND_C8") (pintype "power_in"))
      (node (ref "U2") (pin "E11") (pinfunction "IO,_VREFB7N3_E11") (pintype "bidirectional"))
      (node (ref "U2") (pin "E16") (pinfunction "GND_E16") (pintype "power_in"))
      (node (ref "U2") (pin "E3") (pinfunction "GND_E3") (pintype "power_in"))
      (node (ref "U2") (pin "F1") (pinfunction "CLK1,_DIFFCLK_0n_F1") (pintype "input"))
      (node (ref "U2") (pin "F11") (pinfunction "GND_F11") (pintype "power_in"))
      (node (ref "U2") (pin "F13") (pinfunction "GND_F13") (pintype "power_in"))
      (node (ref "U2") (pin "F2") (pinfunction "CLK0,_DIFFCLK_0p_F2") (pintype "input"))
      (node (ref "U2") (pin "F3") (pinfunction "IO,_VREFB1N1_F3") (pintype "bidirectional"))
      (node (ref "U2") (pin "F7") (pinfunction "GND_F7") (pintype "power_in"))
      (node (ref "U2") (pin "F9") (pinfunction "GND_F9") (pintype "power_in"))
      (node (ref "U2") (pin "G16") (pinfunction "GND_G16") (pintype "power_in"))
      (node (ref "U2") (pin "G3") (pinfunction "GND_G3") (pintype "power_in"))
      (node (ref "U2") (pin "G6") (pinfunction "GND_G6") (pintype "power_in"))
      (node (ref "U2") (pin "G9") (pinfunction "GND_G9") (pintype "power_in"))
      (node (ref "U2") (pin "H10") (pinfunction "GND_H10") (pintype "power_in"))
      (node (ref "U2") (pin "H11") (pinfunction "GND_H11") (pintype "power_in"))
      (node (ref "U2") (pin "H15") (pinfunction "IO,_VREFB6N1_H15") (pintype "bidirectional"))
      (node (ref "U2") (pin "H18") (pinfunction "IO,_VREFB6N2_H18") (pintype "bidirectional"))
      (node (ref "U2") (pin "H3") (pinfunction "IO,_(DATA0)_H3") (pintype "bidirectional"))
      (node (ref "U2") (pin "H4") (pinfunction "DCLK_H4") (pintype "bidirectional"))
      (node (ref "U2") (pin "H6") (pinfunction "IO,_VREFB1N2_H6") (pintype "bidirectional"))
      (node (ref "U2") (pin "H8") (pinfunction "GND_H8") (pintype "power_in"))
      (node (ref "U2") (pin "H9") (pinfunction "GND_H9") (pintype "power_in"))
      (node (ref "U2") (pin "J10") (pinfunction "GND_J10") (pintype "power_in"))
      (node (ref "U2") (pin "J11") (pinfunction "GND_J11") (pintype "power_in"))
      (node (ref "U2") (pin "J13") (pinfunction "IO,_VREFB6N3_J13") (pintype "bidirectional"))
      (node (ref "U2") (pin "J14") (pinfunction "MSEL3_J14") (pintype "input"))
      (node (ref "U2") (pin "J16") (pinfunction "GND_J16") (pintype "power_in"))
      (node (ref "U2") (pin "J17") (pinfunction "MSEL2_J17") (pintype "input"))
      (node (ref "U2") (pin "J18") (pinfunction "MSEL1_J18") (pintype "input"))
      (node (ref "U2") (pin "J3") (pinfunction "GND_J3") (pintype "power_in"))
      (node (ref "U2") (pin "J8") (pinfunction "GND_J8") (pintype "power_in"))
      (node (ref "U2") (pin "J9") (pinfunction "GND_J9") (pintype "power_in"))
      (node (ref "U2") (pin "K10") (pinfunction "GND_K10") (pintype "power_in"))
      (node (ref "U2") (pin "K11") (pinfunction "GND_K11") (pintype "power_in"))
      (node (ref "U2") (pin "K13") (pinfunction "MSEL0_K13") (pintype "input"))
      (node (ref "U2") (pin "K16") (pinfunction "GND_K16") (pintype "power_in"))
      (node (ref "U2") (pin "K3") (pinfunction "GND_K3") (pintype "power_in"))
      (node (ref "U2") (pin "K6") (pinfunction "nCE_K6") (pintype "input"))
      (node (ref "U2") (pin "K8") (pinfunction "GND_K8") (pintype "power_in"))
      (node (ref "U2") (pin "K9") (pinfunction "GND_K9") (pintype "power_in"))
      (node (ref "U2") (pin "L10") (pinfunction "GND_L10") (pintype "power_in"))
      (node (ref "U2") (pin "L11") (pinfunction "GND_L11") (pintype "power_in"))
      (node (ref "U2") (pin "L18") (pinfunction "IO,_VREFB5N0_L18") (pintype "bidirectional"))
      (node (ref "U2") (pin "L6") (pinfunction "IO,_VREFB2N0_L6") (pintype "bidirectional"))
      (node (ref "U2") (pin "L8") (pinfunction "GND_L8") (pintype "power_in"))
      (node (ref "U2") (pin "L9") (pinfunction "GND_L9") (pintype "power_in"))
      (node (ref "U2") (pin "M10") (pinfunction "GND_M10") (pintype "power_in"))
      (node (ref "U2") (pin "M13") (pinfunction "GND_M13") (pintype "power_in"))
      (node (ref "U2") (pin "M16") (pinfunction "GND_M16") (pintype "power_in"))
      (node (ref "U2") (pin "N10") (pinfunction "GND_N10") (pintype "power_in"))
      (node (ref "U2") (pin "N12") (pinfunction "GND_N12") (pintype "power_in"))
      (node (ref "U2") (pin "N16") (pinfunction "IO,_VREFB5N1_N16") (pintype "bidirectional"))
      (node (ref "U2") (pin "N17") (pinfunction "CLK6,_DIFFCLK_3p_N17") (pintype "input"))
      (node (ref "U2") (pin "N18") (pinfunction "CLK7,_DIFFCLK_3n_N18") (pintype "input"))
      (node (ref "U2") (pin "N2") (pinfunction "CLK2,_DIFFCLK_1p_N2") (pintype "input"))
      (node (ref "U2") (pin "N3") (pinfunction "GND_N3") (pintype "power_in"))
      (node (ref "U2") (pin "N6") (pinfunction "GND_N6") (pintype "power_in"))
      (node (ref "U2") (pin "N8") (pinfunction "GND_N8") (pintype "power_in"))
      (node (ref "U2") (pin "P13") (pinfunction "IO,_VREFB4N0_P13") (pintype "bidirectional"))
      (node (ref "U2") (pin "P16") (pinfunction "GND_P16") (pintype "power_in"))
      (node (ref "U2") (pin "P3") (pinfunction "GND_P3") (pintype "power_in"))
      (node (ref "U2") (pin "P8") (pinfunction "IO,_VREFB3N0_P8") (pintype "bidirectional"))
      (node (ref "U2") (pin "R1") (pinfunction "IO,_VREFB2N2_R1") (pintype "bidirectional"))
      (node (ref "U2") (pin "R16") (pinfunction "IO,_RDN3_R16") (pintype "bidirectional"))
      (node (ref "U2") (pin "R17") (pinfunction "IO,_VREFB5N2_R17") (pintype "bidirectional"))
      (node (ref "U2") (pin "R18") (pinfunction "IO,_VREFB5N3_R18") (pintype "bidirectional"))
      (node (ref "U2") (pin "R5") (pinfunction "IO,_VREFB2N3_R5") (pintype "bidirectional"))
      (node (ref "U2") (pin "T1") (pinfunction "IO,_RDN1_T1") (pintype "bidirectional"))
      (node (ref "U2") (pin "T10") (pinfunction "GND_T10") (pintype "power_in"))
      (node (ref "U2") (pin "T11") (pinfunction "IO,_VREFB4N2_T11") (pintype "bidirectional"))
      (node (ref "U2") (pin "T12") (pinfunction "GND_T12") (pintype "power_in"))
      (node (ref "U2") (pin "T13") (pinfunction "IO,_RUP2_T13") (pintype "bidirectional"))
      (node (ref "U2") (pin "T14") (pinfunction "IO,_RDN2_T14") (pintype "bidirectional"))
      (node (ref "U2") (pin "T15") (pinfunction "GND_T15") (pintype "power_in"))
      (node (ref "U2") (pin "T16") (pinfunction "IO,_RUP3,_(DQ3R)/(DQ1R)_T16") (pintype "bidirectional"))
      (node (ref "U2") (pin "T2") (pinfunction "IO,_RUP1_T2") (pintype "bidirectional"))
      (node (ref "U2") (pin "T5") (pinfunction "GND_T5") (pintype "power_in"))
      (node (ref "U2") (pin "T6") (pinfunction "IO,_VREFB3N2_T6") (pintype "bidirectional"))
      (node (ref "U2") (pin "T7") (pinfunction "GND_T7") (pintype "power_in"))
      (node (ref "U2") (pin "T9") (pinfunction "GND_T9") (pintype "power_in"))
      (node (ref "U2") (pin "U10") (pinfunction "CLK13,_DIFFCLK_7p_U10") (pintype "input"))
      (node (ref "U2") (pin "U16") (pinfunction "IO,_VREFB4N1_U16") (pintype "bidirectional"))
      (node (ref "U2") (pin "U18") (pinfunction "IO,_PLL4_CLKOUTp_U18") (pintype "bidirectional"))
      (node (ref "U2") (pin "U2") (pinfunction "IO,_PLL1_CLKOUTp_U2") (pintype "bidirectional"))
      (node (ref "U2") (pin "V10") (pinfunction "CLK12,_DIFFCLK_7n_V10") (pintype "input"))
      (node (ref "U2") (pin "V12") (pinfunction "IO,_VREFB4N3_V12") (pintype "bidirectional"))
      (node (ref "U2") (pin "V18") (pinfunction "IO,_PLL4_CLKOUTn_V18") (pintype "bidirectional"))
      (node (ref "U2") (pin "V2") (pinfunction "IO,_PLL1_CLKOUTn_V2") (pintype "bidirectional"))
      (node (ref "U5") (pin "1") (pinfunction "GND_1") (pintype "power_in"))
      (node (ref "U5") (pin "15") (pinfunction "GND_15") (pintype "power_in"))
      (node (ref "U5") (pin "21") (pinfunction "GND_21") (pintype "power_in"))
      (node (ref "U5") (pin "29") (pinfunction "GND_29") (pintype "power_in"))
      (node (ref "U5") (pin "7") (pinfunction "GND_7") (pintype "power_in"))
    )
    (net (code "117") (name "Hsyn") (class "Default")
      (node (ref "J4") (pin "6") (pinfunction "DATA_6") (pintype "passive"))
      (node (ref "Q2") (pin "3") (pinfunction "D_3") (pintype "passive"))
      (node (ref "R30") (pin "2") (pintype "passive"))
    )
    (net (code "118") (name "Hsync") (class "Default")
      (node (ref "Q2") (pin "2") (pinfunction "S_2") (pintype "passive"))
      (node (ref "R31") (pin "2") (pintype "passive"))
      (node (ref "U2") (pin "A5") (pinfunction "IO,_DIFFIO_T16n,_(DATA14),_(DQS3T/CQ3T#,DPCLK11)/(DQS3T/CQ3T#,DPCLK11)_A5") (pintype "bidirectional"))
    )
    (net (code "119") (name "NetL2_2") (class "Default")
      (node (ref "C26") (pin "1") (pinfunction "1_1") (pintype "passive"))
      (node (ref "C48") (pin "1") (pinfunction "1_1") (pintype "passive"))
      (node (ref "L1") (pin "2") (pinfunction "2_2") (pintype "passive"))
      (node (ref "R25") (pin "2") (pintype "passive"))
      (node (ref "R26") (pin "2") (pintype "passive"))
      (node (ref "U2") (pin "E4") (pinfunction "VCCA3_E4") (pintype "power_in"))
      (node (ref "U2") (pin "F14") (pinfunction "VCCA2_F14") (pintype "power_in"))
      (node (ref "U2") (pin "N14") (pinfunction "VCCA4_N14") (pintype "power_in"))
      (node (ref "U2") (pin "N5") (pinfunction "VCCA1_N5") (pintype "power_in"))
    )
    (net (code "120") (name "Vsyn") (class "Default")
      (node (ref "J5") (pin "6") (pinfunction "DATA_6") (pintype "passive"))
      (node (ref "Q1") (pin "3") (pinfunction "D_3") (pintype "passive"))
      (node (ref "R32") (pin "2") (pintype "passive"))
    )
    (net (code "121") (name "Vsync") (class "Default")
      (node (ref "Q1") (pin "2") (pinfunction "S_2") (pintype "passive"))
      (node (ref "R33") (pin "2") (pintype "passive"))
      (node (ref "U2") (pin "A1") (pinfunction "IO,_PLL3_CLKOUTn_A1") (pintype "bidirectional"))
    )
    (net (code "122") (name "unconnected-(J4-NC-Pad1)") (class "Default")
      (node (ref "J4") (pin "1") (pinfunction "NC_1") (pintype "passive"))
    )
    (net (code "123") (name "unconnected-(J4-NC-Pad4)") (class "Default")
      (node (ref "J4") (pin "4") (pinfunction "NC_4") (pintype "passive"))
    )
    (net (code "124") (name "unconnected-(J4-NC-Pad5)") (class "Default")
      (node (ref "J4") (pin "5") (pinfunction "NC_5") (pintype "passive"))
    )
    (net (code "125") (name "unconnected-(J4-NC-Pad8)") (class "Default")
      (node (ref "J4") (pin "8") (pinfunction "NC_8") (pintype "passive"))
    )
    (net (code "126") (name "unconnected-(J5-NC-Pad1)") (class "Default")
      (node (ref "J5") (pin "1") (pinfunction "NC_1") (pintype "passive"))
    )
    (net (code "127") (name "unconnected-(J5-NC-Pad4)") (class "Default")
      (node (ref "J5") (pin "4") (pinfunction "NC_4") (pintype "passive"))
    )
    (net (code "128") (name "unconnected-(J5-NC-Pad5)") (class "Default")
      (node (ref "J5") (pin "5") (pinfunction "NC_5") (pintype "passive"))
    )
    (net (code "129") (name "unconnected-(J5-NC-Pad8)") (class "Default")
      (node (ref "J5") (pin "8") (pinfunction "NC_8") (pintype "passive"))
    )
    (net (code "130") (name "unconnected-(P1-Pad6)") (class "Default")
      (node (ref "P1") (pin "6") (pinfunction "6_6") (pintype "passive"))
    )
    (net (code "131") (name "unconnected-(P1-Pad7)") (class "Default")
      (node (ref "P1") (pin "7") (pinfunction "7_7") (pintype "passive"))
    )
    (net (code "132") (name "unconnected-(P1-Pad8)") (class "Default")
      (node (ref "P1") (pin "8") (pinfunction "8_8") (pintype "passive"))
    )
    (net (code "133") (name "unconnected-(U2A-IO,_(DQ1L){slash}(DQ1L)-PadC1)") (class "Default")
      (node (ref "U2") (pin "C1") (pinfunction "IO,_(DQ1L)/(DQ1L)_C1") (pintype "bidirectional"))
    )
    (net (code "134") (name "unconnected-(U2A-IO,_(DQS0L{slash}CQ1L,DPCLK0){slash}(DQS0L{slash}CQ1L,DPCLK0)-PadH2)") (class "Default")
      (node (ref "U2") (pin "H2") (pinfunction "IO,_(DQS0L/CQ1L,DPCLK0)/(DQS0L/CQ1L,DPCLK0)_H2") (pintype "bidirectional"))
    )
    (net (code "135") (name "unconnected-(U2A-IO,_(DQS2L{slash}CQ3L,CDPCLK0){slash}(DQS2L{slash}CQ3L,CDPCLK0)-PadD3)") (class "Default")
      (node (ref "U2") (pin "D3") (pinfunction "IO,_(DQS2L/CQ3L,CDPCLK0)/(DQS2L/CQ3L,CDPCLK0)_D3") (pintype "bidirectional"))
    )
    (net (code "136") (name "unconnected-(U2A-IO,_(nRESET)-PadC3)") (class "Default")
      (node (ref "U2") (pin "C3") (pinfunction "IO,_(nRESET)_C3") (pintype "bidirectional"))
    )
    (net (code "137") (name "unconnected-(U2A-IO,_DIFFIO_L8n,_(DATA1,_ASDO)-PadD1)") (class "Default")
      (node (ref "U2") (pin "D1") (pinfunction "IO,_DIFFIO_L8n,_(DATA1,_ASDO)_D1") (pintype "bidirectional"))
    )
    (net (code "138") (name "unconnected-(U2A-IO,_DIFFIO_L10n,_(DQ1L){slash}(DQ1L)-PadE1)") (class "Default")
      (node (ref "U2") (pin "E1") (pinfunction "IO,_DIFFIO_L10n,_(DQ1L)/(DQ1L)_E1") (pintype "bidirectional"))
    )
    (net (code "139") (name "unconnected-(U2A-IO,_DIFFIO_L10p,_(FLASH_nCE,_nCSO)-PadE2)") (class "Default")
      (node (ref "U2") (pin "E2") (pinfunction "IO,_DIFFIO_L10p,_(FLASH_nCE,_nCSO)_E2") (pintype "bidirectional"))
    )
    (net (code "140") (name "unconnected-(U2B-IO,_(DM3L{slash}BWS#3L){slash}(DM1L1{slash}BWS#1L1)-PadR4)") (class "Default")
      (node (ref "U2") (pin "R4") (pinfunction "IO,_(DM3L/BWS#3L)/(DM1L1/BWS#1L1)_R4") (pintype "bidirectional"))
    )
    (net (code "141") (name "unconnected-(U2B-IO,_(DQ3L){slash}(DQ1L)-PadR2)") (class "Default")
      (node (ref "U2") (pin "R2") (pinfunction "IO,_(DQ3L)/(DQ1L)_R2") (pintype "bidirectional"))
    )
    (net (code "142") (name "unconnected-(U2B-IO,_(DQS3L{slash}CQ3L#,CDPCLK1){slash}(DQS3L{slash}CQ3L#,CDPCLK1)-PadM5)") (class "Default")
      (node (ref "U2") (pin "M5") (pinfunction "IO,_(DQS3L/CQ3L#,CDPCLK1)/(DQS3L/CQ3L#,CDPCLK1)_M5") (pintype "bidirectional"))
    )
    (net (code "143") (name "unconnected-(U2B-IO,_DIFFIO_L26n,_(DQ1L){slash}(DQ1L)-PadK1)") (class "Default")
      (node (ref "U2") (pin "K1") (pinfunction "IO,_DIFFIO_L26n,_(DQ1L)/(DQ1L)_K1") (pintype "bidirectional"))
    )
    (net (code "144") (name "unconnected-(U2B-IO,_DIFFIO_L26p,_(DQ1L){slash}(DQ1L)-PadK2)") (class "Default")
      (node (ref "U2") (pin "K2") (pinfunction "IO,_DIFFIO_L26p,_(DQ1L)/(DQ1L)_K2") (pintype "bidirectional"))
    )
    (net (code "145") (name "unconnected-(U2B-IO,_DIFFIO_L28n,_(DM1L{slash}BWS#1L){slash}(DM1L0{slash}BWS#1L0)-PadL5)") (class "Default")
      (node (ref "U2") (pin "L5") (pinfunction "IO,_DIFFIO_L28n,_(DM1L/BWS#1L)/(DM1L0/BWS#1L0)_L5") (pintype "bidirectional"))
    )
    (net (code "146") (name "unconnected-(U2B-IO,_DIFFIO_L28p,_(DQ1L){slash}(DQ1L)-PadK5)") (class "Default")
      (node (ref "U2") (pin "K5") (pinfunction "IO,_DIFFIO_L28p,_(DQ1L)/(DQ1L)_K5") (pintype "bidirectional"))
    )
    (net (code "147") (name "unconnected-(U2B-IO,_DIFFIO_L32n,_(DQ3L){slash}(DQ1L)-PadL1)") (class "Default")
      (node (ref "U2") (pin "L1") (pinfunction "IO,_DIFFIO_L32n,_(DQ3L)/(DQ1L)_L1") (pintype "bidirectional"))
    )
    (net (code "148") (name "unconnected-(U2B-IO,_DIFFIO_L32p,_(DQ3L){slash}(DQ1L)-PadL2)") (class "Default")
      (node (ref "U2") (pin "L2") (pinfunction "IO,_DIFFIO_L32p,_(DQ3L)/(DQ1L)_L2") (pintype "bidirectional"))
    )
    (net (code "149") (name "unconnected-(U2B-IO,_DIFFIO_L33n,_(DQ3L){slash}(DQ1L)-PadL3)") (class "Default")
      (node (ref "U2") (pin "L3") (pinfunction "IO,_DIFFIO_L33n,_(DQ3L)/(DQ1L)_L3") (pintype "bidirectional"))
    )
    (net (code "150") (name "unconnected-(U2B-IO,_DIFFIO_L33p,_(DQ3L){slash}(DQ1L)-PadL4)") (class "Default")
      (node (ref "U2") (pin "L4") (pinfunction "IO,_DIFFIO_L33p,_(DQ3L)/(DQ1L)_L4") (pintype "bidirectional"))
    )
    (net (code "151") (name "unconnected-(U2B-IO,_DIFFIO_L34n-PadM1)") (class "Default")
      (node (ref "U2") (pin "M1") (pinfunction "IO,_DIFFIO_L34n_M1") (pintype "bidirectional"))
    )
    (net (code "152") (name "unconnected-(U2B-IO,_DIFFIO_L34p,_(DQS1L{slash}CQ1L#,DPCLK1){slash}(DQS1L{slash}CQ1L#,DPCLK1)-PadM2)") (class "Default")
      (node (ref "U2") (pin "M2") (pinfunction "IO,_DIFFIO_L34p,_(DQS1L/CQ1L#,DPCLK1)/(DQS1L/CQ1L#,DPCLK1)_M2") (pintype "bidirectional"))
    )
    (net (code "153") (name "unconnected-(U2B-IO,_DIFFIO_L44p,_(DQ3L){slash}(DQ1L)-PadP2)") (class "Default")
      (node (ref "U2") (pin "P2") (pinfunction "IO,_DIFFIO_L44p,_(DQ3L)/(DQ1L)_P2") (pintype "bidirectional"))
    )
    (net (code "154") (name "unconnected-(U2B-IO,_DIFFIO_L52n,_(DQ3L){slash}(DQ1L)-PadR3)") (class "Default")
      (node (ref "U2") (pin "R3") (pinfunction "IO,_DIFFIO_L52n,_(DQ3L)/(DQ1L)_R3") (pintype "bidirectional"))
    )
    (net (code "155") (name "unconnected-(U2B-IO,_DIFFIO_L52p,_(DQ3L){slash}(DQ1L)-PadT3)") (class "Default")
      (node (ref "U2") (pin "T3") (pinfunction "IO,_DIFFIO_L52p,_(DQ3L)/(DQ1L)_T3") (pintype "bidirectional"))
    )
    (net (code "156") (name "unconnected-(U2C-IO,_(DQ3B){slash}(DQ5B)-PadP9)") (class "Default")
      (node (ref "U2") (pin "P9") (pinfunction "IO,_(DQ3B)/(DQ5B)_P9") (pintype "bidirectional"))
    )
    (net (code "157") (name "unconnected-(U2C-IO,_DIFFIO_B1n-PadV1)") (class "Default")
      (node (ref "U2") (pin "V1") (pinfunction "IO,_DIFFIO_B1n_V1") (pintype "bidirectional"))
    )
    (net (code "158") (name "unconnected-(U2C-IO,_DIFFIO_B16n,_(DM3B{slash}BWS#3B){slash}(DM5B1{slash}BWS#5B1)-PadV3)") (class "Default")
      (node (ref "U2") (pin "V3") (pinfunction "IO,_DIFFIO_B16n,_(DM3B/BWS#3B)/(DM5B1/BWS#5B1)_V3") (pintype "bidirectional"))
    )
    (net (code "159") (name "unconnected-(U2C-IO,_DIFFIO_B18n,_(DQ3B){slash}(DQ5B)-PadV5)") (class "Default")
      (node (ref "U2") (pin "V5") (pinfunction "IO,_DIFFIO_B18n,_(DQ3B)/(DQ5B)_V5") (pintype "bidirectional"))
    )
    (net (code "160") (name "unconnected-(U2C-IO,_DIFFIO_B18p-PadU5)") (class "Default")
      (node (ref "U2") (pin "U5") (pinfunction "IO,_DIFFIO_B18p_U5") (pintype "bidirectional"))
    )
    (net (code "161") (name "unconnected-(U2C-IO,_DIFFIO_B21n,_(DQS5B{slash}CQ5B#,DPCLK3){slash}(DQS5B{slash}CQ5B#,DPCLK3)-PadT8)") (class "Default")
      (node (ref "U2") (pin "T8") (pinfunction "IO,_DIFFIO_B21n,_(DQS5B/CQ5B#,DPCLK3)/(DQS5B/CQ5B#,DPCLK3)_T8") (pintype "bidirectional"))
    )
    (net (code "162") (name "unconnected-(U2C-IO,_DIFFIO_B21p,_(DQ3B){slash}(DQ5B)-PadR8)") (class "Default")
      (node (ref "U2") (pin "R8") (pinfunction "IO,_DIFFIO_B21p,_(DQ3B)/(DQ5B)_R8") (pintype "bidirectional"))
    )
    (net (code "163") (name "unconnected-(U2C-IO,_DIFFIO_B24n,_(DQ3B){slash}(DQ5B)-PadV6)") (class "Default")
      (node (ref "U2") (pin "V6") (pinfunction "IO,_DIFFIO_B24n,_(DQ3B)/(DQ5B)_V6") (pintype "bidirectional"))
    )
    (net (code "164") (name "unconnected-(U2C-IO,_DIFFIO_B24p,_(DQ3B){slash}(DQ5B)-PadU6)") (class "Default")
      (node (ref "U2") (pin "U6") (pinfunction "IO,_DIFFIO_B24p,_(DQ3B)/(DQ5B)_U6") (pintype "bidirectional"))
    )
    (net (code "165") (name "unconnected-(U2D-IO,_(DQ5B){slash}(DQ5B)-PadR11)") (class "Default")
      (node (ref "U2") (pin "R11") (pinfunction "IO,_(DQ5B)/(DQ5B)_R11") (pintype "bidirectional"))
    )
    (net (code "166") (name "unconnected-(U2D-IO,_(DQ5B){slash}(DQ5B)-PadU12)") (class "Default")
      (node (ref "U2") (pin "U12") (pinfunction "IO,_(DQ5B)/(DQ5B)_U12") (pintype "bidirectional"))
    )
    (net (code "167") (name "unconnected-(U2D-IO,_(DQ5B){slash}(DQ5B)-PadV16)") (class "Default")
      (node (ref "U2") (pin "V16") (pinfunction "IO,_(DQ5B)/(DQ5B)_V16") (pintype "bidirectional"))
    )
    (net (code "168") (name "unconnected-(U2D-IO,_(DQS0B{slash}CQ1B,CDPCLK3){slash}(DQS0B{slash}CQ1B,CDPCLK3)-PadR13)") (class "Default")
      (node (ref "U2") (pin "R13") (pinfunction "IO,_(DQS0B/CQ1B,CDPCLK3)/(DQS0B/CQ1B,CDPCLK3)_R13") (pintype "bidirectional"))
    )
    (net (code "169") (name "unconnected-(U2D-IO,_(DQS2B{slash}CQ3B,DPCLK5){slash}(DQS2B{slash}CQ3B,DPCLK5)-PadP12)") (class "Default")
      (node (ref "U2") (pin "P12") (pinfunction "IO,_(DQS2B/CQ3B,DPCLK5)/(DQS2B/CQ3B,DPCLK5)_P12") (pintype "bidirectional"))
    )
    (net (code "170") (name "unconnected-(U2D-IO,_DIFFIO_B35n,_(DQ5B){slash}(DQ5B)-PadV15)") (class "Default")
      (node (ref "U2") (pin "V15") (pinfunction "IO,_DIFFIO_B35n,_(DQ5B)/(DQ5B)_V15") (pintype "bidirectional"))
    )
    (net (code "171") (name "unconnected-(U2D-IO,_DIFFIO_B35p-PadU15)") (class "Default")
      (node (ref "U2") (pin "U15") (pinfunction "IO,_DIFFIO_B35p_U15") (pintype "bidirectional"))
    )
    (net (code "172") (name "unconnected-(U2D-IO,_DIFFIO_B47p-PadU17)") (class "Default")
      (node (ref "U2") (pin "U17") (pinfunction "IO,_DIFFIO_B47p_U17") (pintype "bidirectional"))
    )
    (net (code "173") (name "unconnected-(U2E-IO,_(DQ3R){slash}(DQ1R)-PadT17)") (class "Default")
      (node (ref "U2") (pin "T17") (pinfunction "IO,_(DQ3R)/(DQ1R)_T17") (pintype "bidirectional"))
    )
    (net (code "174") (name "unconnected-(U2F-IO,_(DQ1R){slash}(DQ1R)-PadH17)") (class "Default")
      (node (ref "U2") (pin "H17") (pinfunction "IO,_(DQ1R)/(DQ1R)_H17") (pintype "bidirectional"))
    )
    (net (code "175") (name "unconnected-(U2F-IO,_(PADD20),_(DQS2R{slash}CQ3R,CDPCLK5){slash}(DQS2R{slash}CQ3R,CDPCLK5)-PadB18)") (class "Default")
      (node (ref "U2") (pin "B18") (pinfunction "IO,_(PADD20),_(DQS2R/CQ3R,CDPCLK5)/(DQS2R/CQ3R,CDPCLK5)_B18") (pintype "bidirectional"))
    )
    (net (code "176") (name "unconnected-(U2F-IO,_(PADD23),_(DQ1R){slash}(DQ1R)-PadG14)") (class "Default")
      (node (ref "U2") (pin "G14") (pinfunction "IO,_(PADD23),_(DQ1R)/(DQ1R)_G14") (pintype "bidirectional"))
    )
    (net (code "177") (name "unconnected-(U2F-IO,_DIFFIO_R24n,_(nCEO)-PadE18)") (class "Default")
      (node (ref "U2") (pin "E18") (pinfunction "IO,_DIFFIO_R24n,_(nCEO)_E18") (pintype "bidirectional"))
    )
    (net (code "178") (name "unconnected-(U2F-IO,_DIFFIO_R24p,_(CLKUSR)-PadE17)") (class "Default")
      (node (ref "U2") (pin "E17") (pinfunction "IO,_DIFFIO_R24p,_(CLKUSR)_E17") (pintype "bidirectional"))
    )
    (net (code "179") (name "unconnected-(U2G-IO,_(PADD4),_(DQS2T{slash}CQ3T,DPCLK8){slash}(DQS2T{slash}CQ3T,DPCLK8)-PadB15)") (class "Default")
      (node (ref "U2") (pin "B15") (pinfunction "IO,_(PADD4),_(DQS2T/CQ3T,DPCLK8)/(DQS2T/CQ3T,DPCLK8)_B15") (pintype "bidirectional"))
    )
    (net (code "180") (name "unconnected-(U2G-IO,_DIFFIO_T27n,_(PADD13),_(DM5T{slash}BWS#5T){slash}(DM5T0{slash}BWS#5T0)-PadC10)") (class "Default")
      (node (ref "U2") (pin "C10") (pinfunction "IO,_DIFFIO_T27n,_(PADD13),_(DM5T/BWS#5T)/(DM5T0/BWS#5T0)_C10") (pintype "bidirectional"))
    )
    (net (code "181") (name "unconnected-(U2G-IO,_DIFFIO_T27p,_(PADD14)-PadD10)") (class "Default")
      (node (ref "U2") (pin "D10") (pinfunction "IO,_DIFFIO_T27p,_(PADD14)_D10") (pintype "bidirectional"))
    )
    (net (code "182") (name "unconnected-(U2G-IO,_DIFFIO_T29p,_(PADD12),_(DQS4T{slash}CQ5T,DPCLK9){slash}(DQS4T{slash}CQ5T,DPCLK9)-PadB11)") (class "Default")
      (node (ref "U2") (pin "B11") (pinfunction "IO,_DIFFIO_T29p,_(PADD12),_(DQS4T/CQ5T,DPCLK9)/(DQS4T/CQ5T,DPCLK9)_B11") (pintype "bidirectional"))
    )
    (net (code "183") (name "unconnected-(U2G-IO,_DIFFIO_T35p,_(PADD8),_(DQ5T){slash}(DQ5T)-PadB13)") (class "Default")
      (node (ref "U2") (pin "B13") (pinfunction "IO,_DIFFIO_T35p,_(PADD8),_(DQ5T)/(DQ5T)_B13") (pintype "bidirectional"))
    )
    (net (code "184") (name "unconnected-(U2G-IO,_DIFFIO_T41p,_(PADD2),_(DQ5T){slash}(DQ5T)-PadB16)") (class "Default")
      (node (ref "U2") (pin "B16") (pinfunction "IO,_DIFFIO_T41p,_(PADD2),_(DQ5T)/(DQ5T)_B16") (pintype "bidirectional"))
    )
    (net (code "185") (name "unconnected-(U2H-IO,_(DATA5),_(DQ3T){slash}(DQ5T)-PadC5)") (class "Default")
      (node (ref "U2") (pin "C5") (pinfunction "IO,_(DATA5),_(DQ3T)/(DQ5T)_C5") (pintype "bidirectional"))
    )
    (net (code "186") (name "unconnected-(U2H-IO,_DIFFIO_T16p,_(DATA13)-PadB5)") (class "Default")
      (node (ref "U2") (pin "B5") (pinfunction "IO,_DIFFIO_T16p,_(DATA13)_B5") (pintype "bidirectional"))
    )
    (net (code "187") (name "unconnected-(U2H-IO,_DIFFIO_T19p,_(DATA4),_(DQ3T){slash}(DQ5T)-PadB7)") (class "Default")
      (node (ref "U2") (pin "B7") (pinfunction "IO,_DIFFIO_T19p,_(DATA4),_(DQ3T)/(DQ5T)_B7") (pintype "bidirectional"))
    )
    (net (code "188") (name "unconnected-(U5-NC-Pad11)") (class "Default")
      (node (ref "U5") (pin "11") (pinfunction "NC_11") (pintype "passive"))
    )
    (net (code "189") (name "unconnected-(U5-NINT-Pad10)") (class "Default")
      (node (ref "U5") (pin "10") (pinfunction "NINT_10") (pintype "output"))
    )
  )
)
